# Schematic.net
KiCad netlist of a schematic drawn in Altium Designer
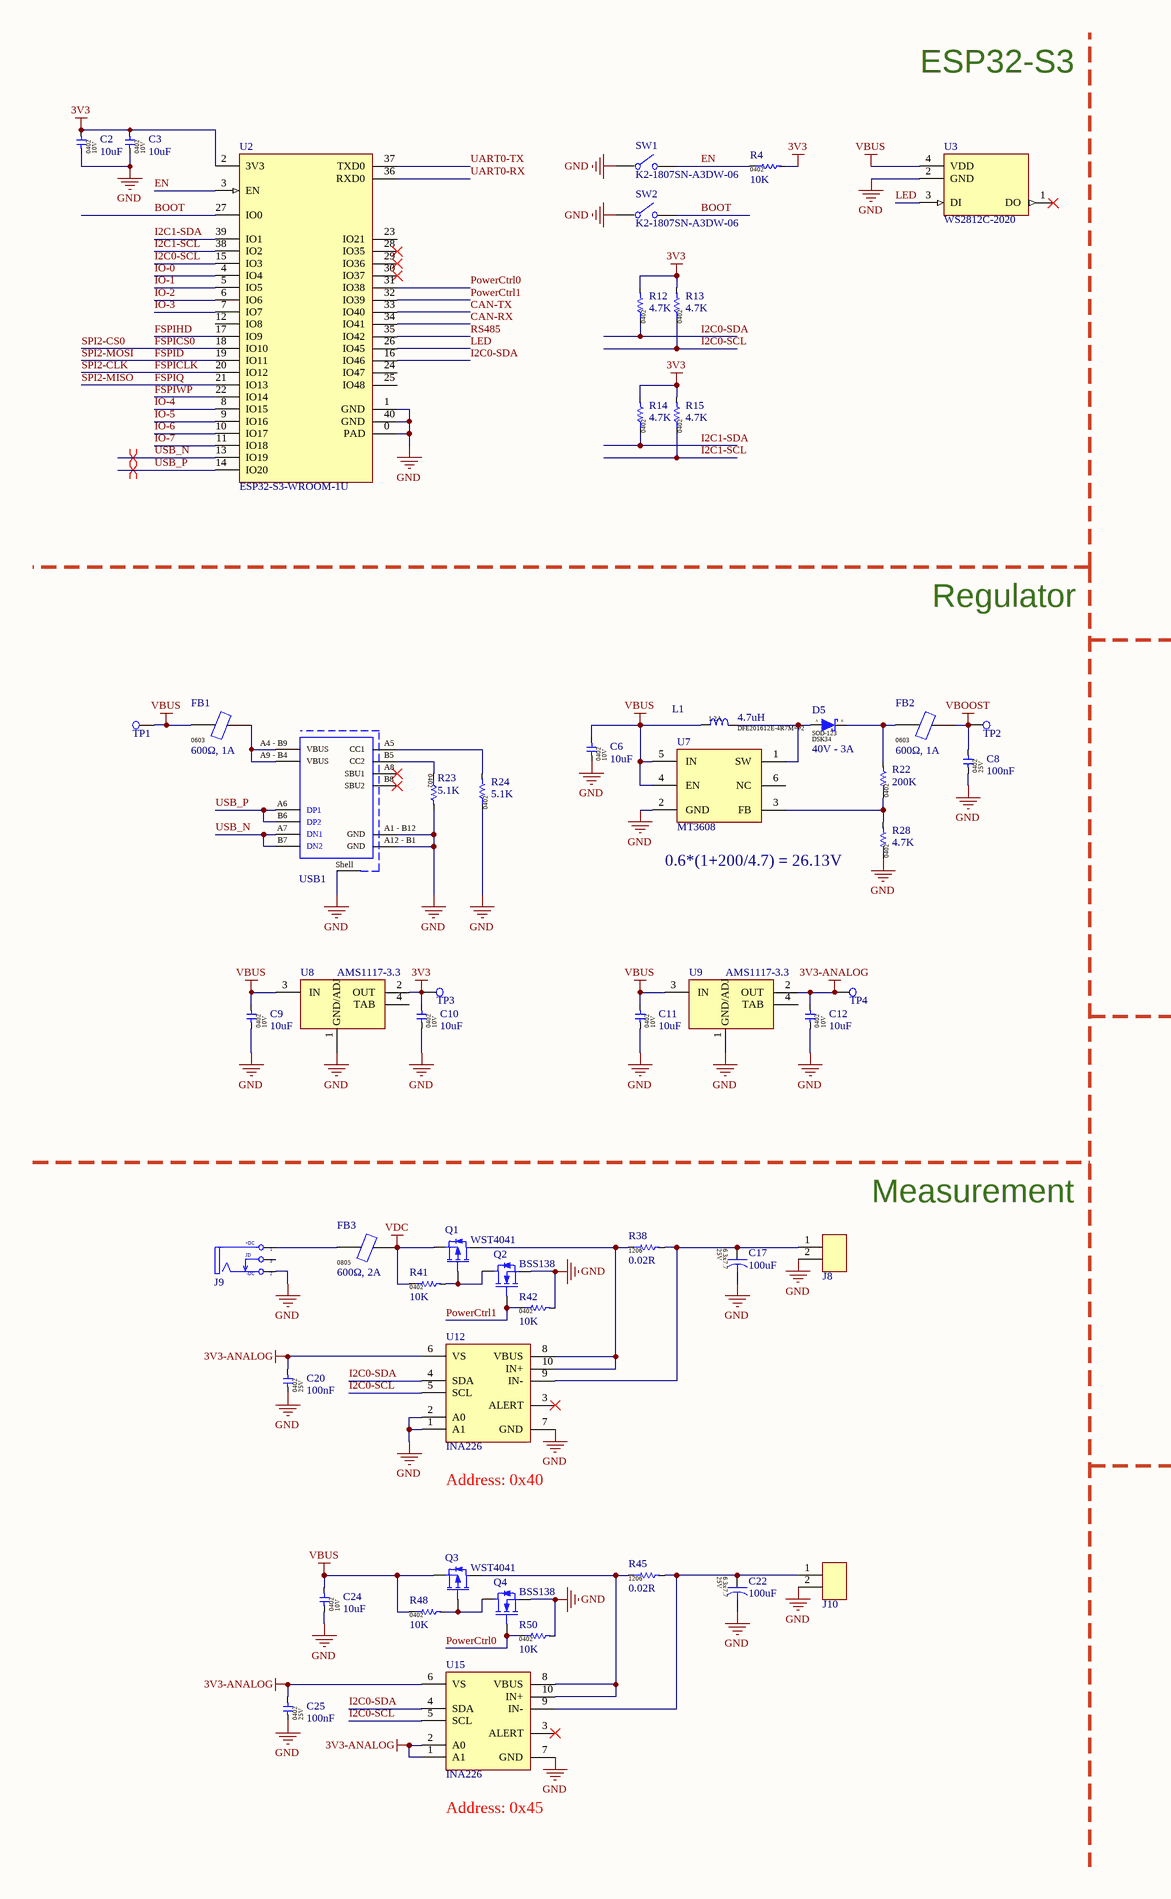
[diagram p0: Schematic.SchDoc, left]
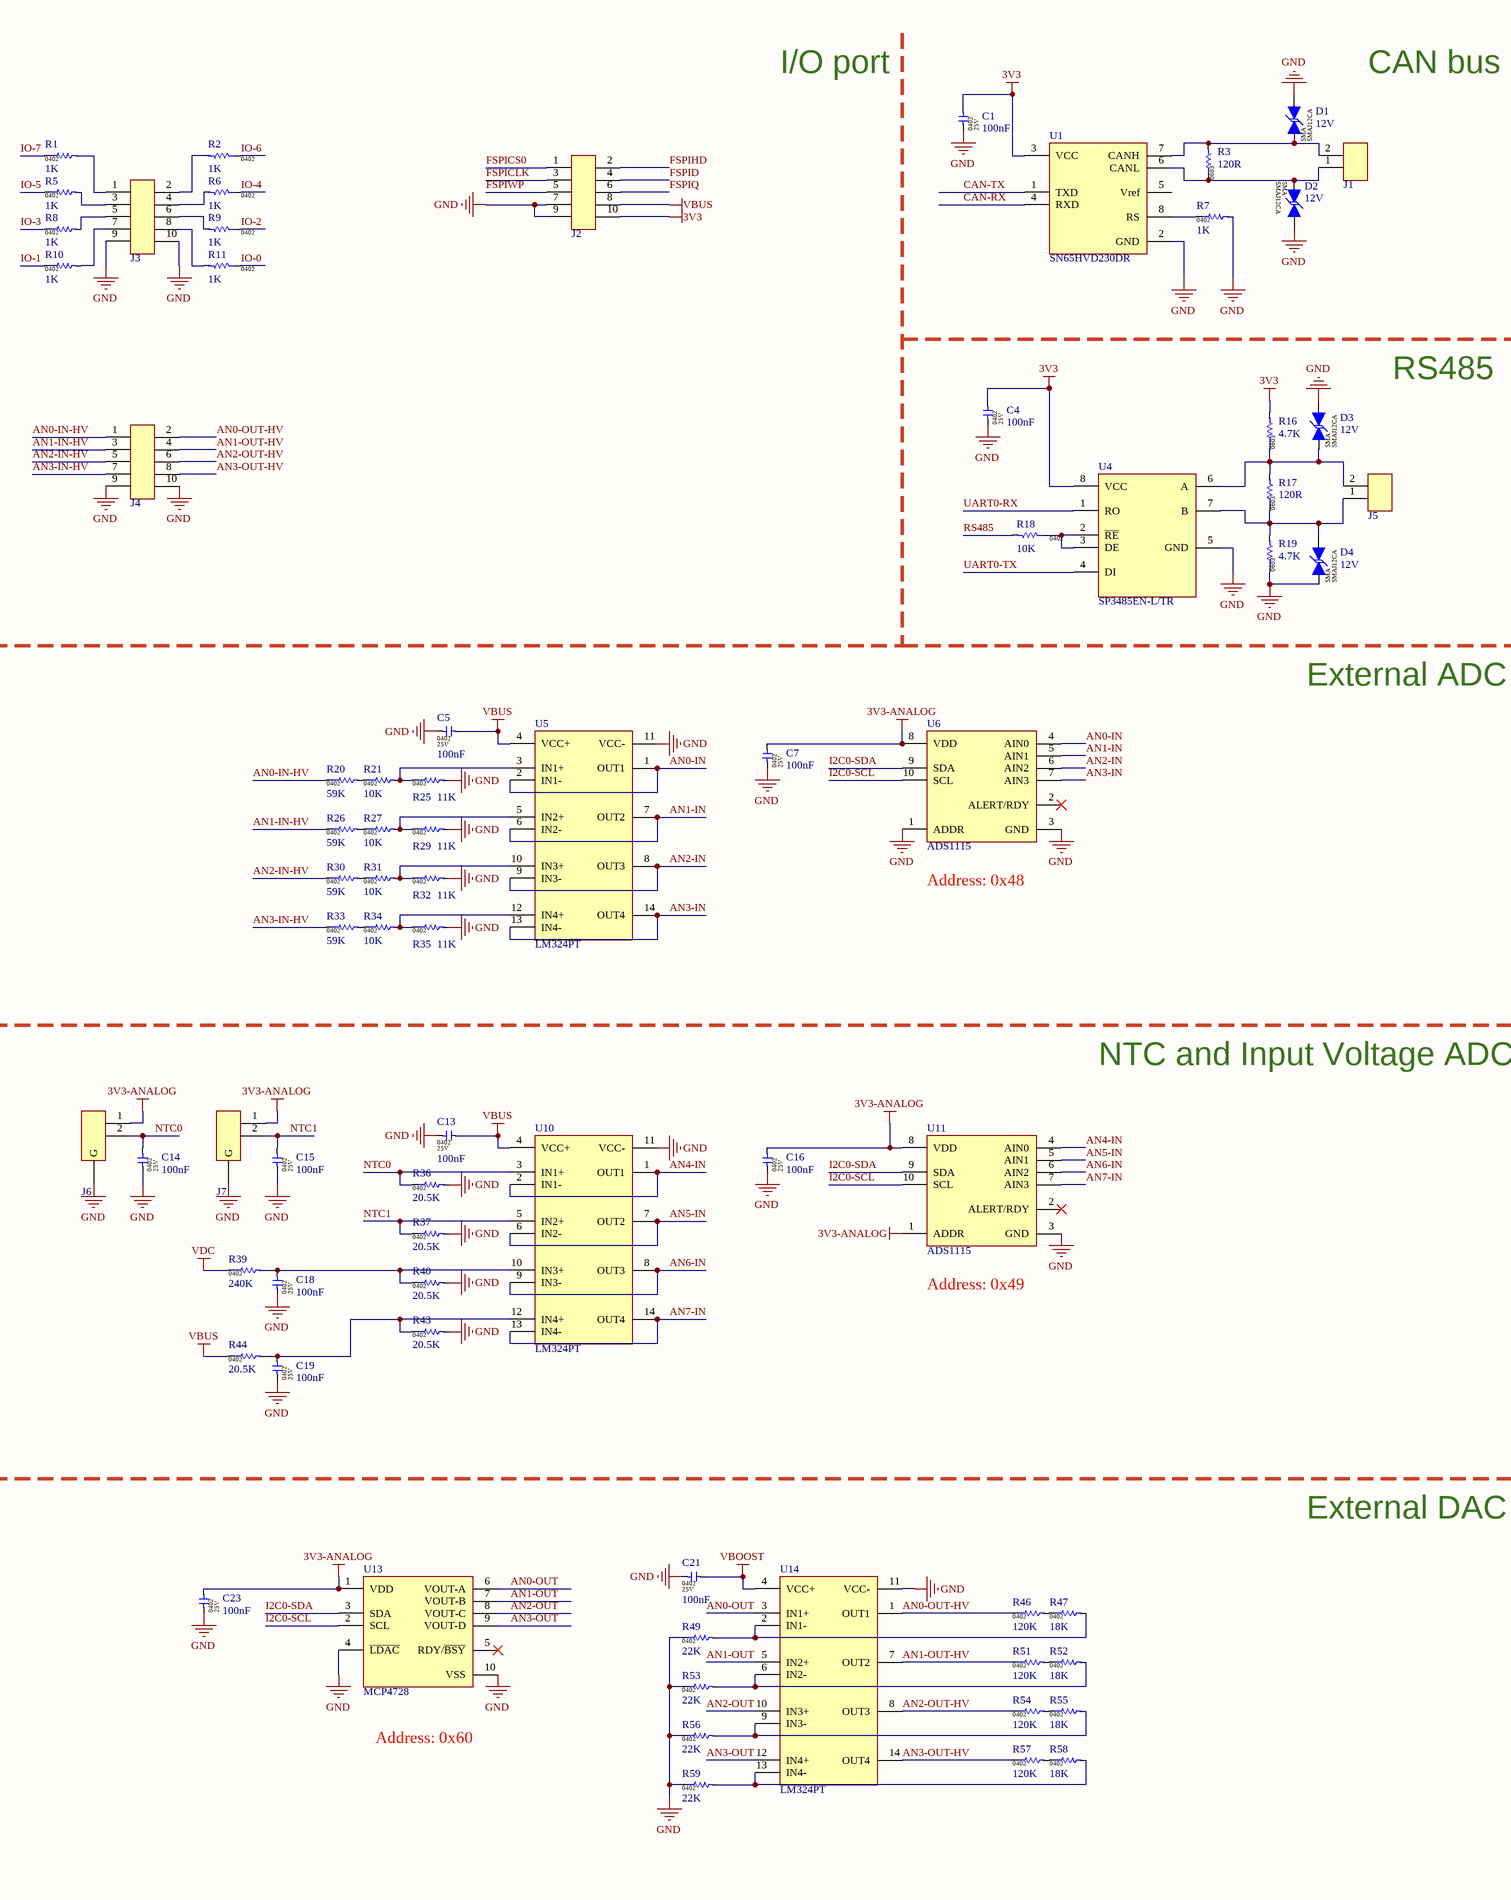
[diagram p1: Schematic.SchDoc, right]

(export (version "E")
  (design (tool "Eeschema 10.0.6"))
  (components
    (comp (ref "C1")
      (value "100nF")
      (footprint "CAP-0402")
      (description "100nF ±10% 25V X5R 0402 Multilayer Ceramic Capacitors MLCC - SMD/SMT RoHS")
      (fields (field (name "MANUFACTURE PART") "0402X104K250CT") (field (name "VOLTAGE") "25V"))
      (libsource (lib "Capacitor Database") (part "Cap-non-polarized"))
    )
    (comp (ref "C2")
      (value "10uF")
      (footprint "CAP-0402")
      (description "10V 10uF X5R ±20% 0402 Multilayer Ceramic Capacitors MLCC - SMD/SMT ROHS")
      (fields (field (name "MANUFACTURE PART") "CL05A106MP5NUNC") (field (name "VOLTAGE") "10V"))
      (libsource (lib "Capacitor Database") (part "Cap-non-polarized"))
    )
    (comp (ref "C3")
      (value "10uF")
      (footprint "CAP-0402")
      (description "10V 10uF X5R ±20% 0402 Multilayer Ceramic Capacitors MLCC - SMD/SMT ROHS")
      (fields (field (name "MANUFACTURE PART") "CL05A106MP5NUNC") (field (name "VOLTAGE") "10V"))
      (libsource (lib "Capacitor Database") (part "Cap-non-polarized"))
    )
    (comp (ref "C4")
      (value "100nF")
      (footprint "CAP-0402")
      (description "100nF ±10% 25V X5R 0402 Multilayer Ceramic Capacitors MLCC - SMD/SMT RoHS")
      (fields (field (name "MANUFACTURE PART") "0402X104K250CT") (field (name "VOLTAGE") "25V"))
      (libsource (lib "Capacitor Database") (part "Cap-non-polarized"))
    )
    (comp (ref "C5")
      (value "100nF")
      (footprint "CAP-0402")
      (description "100nF ±10% 25V X5R 0402 Multilayer Ceramic Capacitors MLCC - SMD/SMT RoHS")
      (fields (field (name "MANUFACTURE PART") "0402X104K250CT") (field (name "VOLTAGE") "25V"))
      (libsource (lib "Capacitor Database") (part "Cap-non-polarized"))
    )
    (comp (ref "C6")
      (value "10uF")
      (footprint "CAP-0402")
      (description "10V 10uF X5R ±20% 0402 Multilayer Ceramic Capacitors MLCC - SMD/SMT ROHS")
      (fields (field (name "MANUFACTURE PART") "CL05A106MP5NUNC") (field (name "VOLTAGE") "10V"))
      (libsource (lib "Capacitor Database") (part "Cap-non-polarized"))
    )
    (comp (ref "C7")
      (value "100nF")
      (footprint "CAP-0402")
      (description "100nF ±10% 25V X5R 0402 Multilayer Ceramic Capacitors MLCC - SMD/SMT RoHS")
      (fields (field (name "MANUFACTURE PART") "0402X104K250CT") (field (name "VOLTAGE") "25V"))
      (libsource (lib "Capacitor Database") (part "Cap-non-polarized"))
    )
    (comp (ref "C8")
      (value "100nF")
      (footprint "CAP-0402")
      (description "100nF ±10% 25V X5R 0402 Multilayer Ceramic Capacitors MLCC - SMD/SMT RoHS")
      (fields (field (name "MANUFACTURE PART") "0402X104K250CT") (field (name "VOLTAGE") "25V"))
      (libsource (lib "Capacitor Database") (part "Cap-non-polarized"))
    )
    (comp (ref "C9")
      (value "10uF")
      (footprint "CAP-0402")
      (description "10V 10uF X5R ±20% 0402 Multilayer Ceramic Capacitors MLCC - SMD/SMT ROHS")
      (fields (field (name "MANUFACTURE PART") "CL05A106MP5NUNC") (field (name "VOLTAGE") "10V"))
      (libsource (lib "Capacitor Database") (part "Cap-non-polarized"))
    )
    (comp (ref "C10")
      (value "10uF")
      (footprint "CAP-0402")
      (description "10V 10uF X5R ±20% 0402 Multilayer Ceramic Capacitors MLCC - SMD/SMT ROHS")
      (fields (field (name "MANUFACTURE PART") "CL05A106MP5NUNC") (field (name "VOLTAGE") "10V"))
      (libsource (lib "Capacitor Database") (part "Cap-non-polarized"))
    )
    (comp (ref "C11")
      (value "10uF")
      (footprint "CAP-0402")
      (description "10V 10uF X5R ±20% 0402 Multilayer Ceramic Capacitors MLCC - SMD/SMT ROHS")
      (fields (field (name "MANUFACTURE PART") "CL05A106MP5NUNC") (field (name "VOLTAGE") "10V"))
      (libsource (lib "Capacitor Database") (part "Cap-non-polarized"))
    )
    (comp (ref "C12")
      (value "10uF")
      (footprint "CAP-0402")
      (description "10V 10uF X5R ±20% 0402 Multilayer Ceramic Capacitors MLCC - SMD/SMT ROHS")
      (fields (field (name "MANUFACTURE PART") "CL05A106MP5NUNC") (field (name "VOLTAGE") "10V"))
      (libsource (lib "Capacitor Database") (part "Cap-non-polarized"))
    )
    (comp (ref "C13")
      (value "100nF")
      (footprint "CAP-0402")
      (description "100nF ±10% 25V X5R 0402 Multilayer Ceramic Capacitors MLCC - SMD/SMT RoHS")
      (fields (field (name "MANUFACTURE PART") "0402X104K250CT") (field (name "VOLTAGE") "25V"))
      (libsource (lib "Capacitor Database") (part "Cap-non-polarized"))
    )
    (comp (ref "C14")
      (value "100nF")
      (footprint "CAP-0402")
      (description "100nF ±10% 25V X5R 0402 Multilayer Ceramic Capacitors MLCC - SMD/SMT RoHS")
      (fields (field (name "MANUFACTURE PART") "0402X104K250CT") (field (name "VOLTAGE") "25V"))
      (libsource (lib "Capacitor Database") (part "Cap-non-polarized"))
    )
    (comp (ref "C15")
      (value "100nF")
      (footprint "CAP-0402")
      (description "100nF ±10% 25V X5R 0402 Multilayer Ceramic Capacitors MLCC - SMD/SMT RoHS")
      (fields (field (name "MANUFACTURE PART") "0402X104K250CT") (field (name "VOLTAGE") "25V"))
      (libsource (lib "Capacitor Database") (part "Cap-non-polarized"))
    )
    (comp (ref "C16")
      (value "100nF")
      (footprint "CAP-0402")
      (description "100nF ±10% 25V X5R 0402 Multilayer Ceramic Capacitors MLCC - SMD/SMT RoHS")
      (fields (field (name "MANUFACTURE PART") "0402X104K250CT") (field (name "VOLTAGE") "25V"))
      (libsource (lib "Capacitor Database") (part "Cap-non-polarized"))
    )
    (comp (ref "C17")
      (value "100uF")
      (footprint "CAP-ALU-SMD-D")
      (fields (field (name "MANUFACTURE PART") "RVT1E101M0607") (field (name "VOLTAGE") "25V"))
      (libsource (lib "Capacitor Database") (part "Cap-polarized"))
    )
    (comp (ref "C18")
      (value "100nF")
      (footprint "CAP-0402")
      (description "100nF ±10% 25V X5R 0402 Multilayer Ceramic Capacitors MLCC - SMD/SMT RoHS")
      (fields (field (name "MANUFACTURE PART") "0402X104K250CT") (field (name "VOLTAGE") "25V"))
      (libsource (lib "Capacitor Database") (part "Cap-non-polarized"))
    )
    (comp (ref "C19")
      (value "100nF")
      (footprint "CAP-0402")
      (description "100nF ±10% 25V X5R 0402 Multilayer Ceramic Capacitors MLCC - SMD/SMT RoHS")
      (fields (field (name "MANUFACTURE PART") "0402X104K250CT") (field (name "VOLTAGE") "25V"))
      (libsource (lib "Capacitor Database") (part "Cap-non-polarized"))
    )
    (comp (ref "C20")
      (value "100nF")
      (footprint "CAP-0402")
      (description "100nF ±10% 25V X5R 0402 Multilayer Ceramic Capacitors MLCC - SMD/SMT RoHS")
      (fields (field (name "MANUFACTURE PART") "0402X104K250CT") (field (name "VOLTAGE") "25V"))
      (libsource (lib "Capacitor Database") (part "Cap-non-polarized"))
    )
    (comp (ref "C21")
      (value "100nF")
      (footprint "CAP-0402")
      (description "100nF ±10% 25V X5R 0402 Multilayer Ceramic Capacitors MLCC - SMD/SMT RoHS")
      (fields (field (name "MANUFACTURE PART") "0402X104K250CT") (field (name "VOLTAGE") "25V"))
      (libsource (lib "Capacitor Database") (part "Cap-non-polarized"))
    )
    (comp (ref "C22")
      (value "100uF")
      (footprint "CAP-ALU-SMD-D")
      (fields (field (name "MANUFACTURE PART") "RVT1E101M0607") (field (name "VOLTAGE") "25V"))
      (libsource (lib "Capacitor Database") (part "Cap-polarized"))
    )
    (comp (ref "C23")
      (value "100nF")
      (footprint "CAP-0402")
      (description "100nF ±10% 25V X5R 0402 Multilayer Ceramic Capacitors MLCC - SMD/SMT RoHS")
      (fields (field (name "MANUFACTURE PART") "0402X104K250CT") (field (name "VOLTAGE") "25V"))
      (libsource (lib "Capacitor Database") (part "Cap-non-polarized"))
    )
    (comp (ref "C24")
      (value "10uF")
      (footprint "CAP-0402")
      (description "10V 10uF X5R ±20% 0402 Multilayer Ceramic Capacitors MLCC - SMD/SMT ROHS")
      (fields (field (name "MANUFACTURE PART") "CL05A106MP5NUNC") (field (name "VOLTAGE") "10V"))
      (libsource (lib "Capacitor Database") (part "Cap-non-polarized"))
    )
    (comp (ref "C25")
      (value "100nF")
      (footprint "CAP-0402")
      (description "100nF ±10% 25V X5R 0402 Multilayer Ceramic Capacitors MLCC - SMD/SMT RoHS")
      (fields (field (name "MANUFACTURE PART") "0402X104K250CT") (field (name "VOLTAGE") "25V"))
      (libsource (lib "Capacitor Database") (part "Cap-non-polarized"))
    )
    (comp (ref "D1")
      (value "12V")
      (footprint "SMA-DO-214AC (BI)")
      (description "ESD Suppressors / TVS Diodes 400W 12V 5% Bi-Directional")
      (fields (field (name "MANUFACTURE PART") "SMAJ12CA"))
      (libsource (lib "Diode Database") (part "TVS/ESD Bi diode"))
    )
    (comp (ref "D2")
      (value "12V")
      (footprint "SMA-DO-214AC (BI)")
      (description "ESD Suppressors / TVS Diodes 400W 12V 5% Bi-Directional")
      (fields (field (name "MANUFACTURE PART") "SMAJ12CA"))
      (libsource (lib "Diode Database") (part "TVS/ESD Bi diode"))
    )
    (comp (ref "D3")
      (value "12V")
      (footprint "SMA-DO-214AC (BI)")
      (description "ESD Suppressors / TVS Diodes 400W 12V 5% Bi-Directional")
      (fields (field (name "MANUFACTURE PART") "SMAJ12CA"))
      (libsource (lib "Diode Database") (part "TVS/ESD Bi diode"))
    )
    (comp (ref "D4")
      (value "12V")
      (footprint "SMA-DO-214AC (BI)")
      (description "ESD Suppressors / TVS Diodes 400W 12V 5% Bi-Directional")
      (fields (field (name "MANUFACTURE PART") "SMAJ12CA"))
      (libsource (lib "Diode Database") (part "TVS/ESD Bi diode"))
    )
    (comp (ref "D5")
      (value "40V - 3A")
      (footprint "SOD123")
      (description "40V 3A 550mV @ 3A SOD-123 Schottky Barrier Diodes (SBD) RoHS")
      (fields (field (name "MANUFACTURE PART") "DSK34"))
      (libsource (lib "Diode Database") (part "Schottky diode"))
    )
    (comp (ref "FB1")
      (value "600Ω, 1A")
      (footprint "Ferrite-0603")
      (description "600Ω @ 100MHz 1A 1 150mΩ 0603 Ferrite Beads RoHS")
      (fields (field (name "MANUFACTURE PART") "UPZ1608E601-1R0TF"))
      (libsource (lib "Filter Database") (part "Ferrite Beads"))
    )
    (comp (ref "FB2")
      (value "600Ω, 1A")
      (footprint "Ferrite-0603")
      (description "600Ω @ 100MHz 1A 1 150mΩ 0603 Ferrite Beads RoHS")
      (fields (field (name "MANUFACTURE PART") "UPZ1608E601-1R0TF"))
      (libsource (lib "Filter Database") (part "Ferrite Beads"))
    )
    (comp (ref "FB3")
      (value "600Ω, 2A")
      (footprint "Ferrite-0805")
      (description "600Ω @ 100MHz 2A ±25% 0805 Ferrite Beads ROHS")
      (fields (field (name "MANUFACTURE PART") "CBM201209U601T"))
      (libsource (lib "Filter Database") (part "Ferrite Beads"))
    )
    (comp (ref "J1")
      (value "DB301V-5.0-2P-BU-S")
      (footprint "Terminal block 2P 5.0")
      (description "1.5 -40℃~+120℃ 17.5A 250V Blue Straight pin 5mm, Screw terminal ROHS")
      (libsource (lib "") (part "Conn-2P_1"))
    )
    (comp (ref "J2")
      (value "IDC2.54-05-05PWS")
      (footprint "Conn IDC 10P-2.54H right")
      (libsource (lib "Connectors, Misc") (part "Conn-10P-2x5P"))
    )
    (comp (ref "J3")
      (value "IDC2.54-05-05PWS")
      (footprint "Conn IDC 10P-2.54H right")
      (libsource (lib "Connectors, Misc") (part "Conn-10P-2x5P"))
    )
    (comp (ref "J4")
      (value "IDC2.54-05-05PWS")
      (footprint "Conn IDC 10P-2.54H right")
      (libsource (lib "Connectors, Misc") (part "Conn-10P-2x5P"))
    )
    (comp (ref "J5")
      (value "DB301V-5.0-2P-BU-S")
      (footprint "Terminal block 2P 5.0")
      (description "1.5 -40℃~+120℃ 17.5A 250V Blue Straight pin 5mm, Screw terminal ROHS")
      (libsource (lib "") (part "Conn-2P_1"))
    )
    (comp (ref "J6")
      (value "S2B-XH-SM4-TB(LF)(SN)")
      (footprint "XH-2.54-2Pin-SMT")
      (description "XH Header Male Pin 0.098\"(2.50mm) 2 SMD,P=2.5mm Wire To Board / Wire To Wire Connector RoHS")
      (libsource (lib "Connectors, Misc") (part "Conn-2P_PAD"))
    )
    (comp (ref "J7")
      (value "S2B-XH-SM4-TB(LF)(SN)")
      (footprint "XH-2.54-2Pin-SMT")
      (description "XH Header Male Pin 0.098\"(2.50mm) 2 SMD,P=2.5mm Wire To Board / Wire To Wire Connector RoHS")
      (libsource (lib "Connectors, Misc") (part "Conn-2P_PAD"))
    )
    (comp (ref "J8")
      (value "DB301V-5.0-2P-BU-S")
      (footprint "Terminal block 2P 5.0")
      (description "1.5 -40℃~+120℃ 17.5A 250V Blue Straight pin 5mm, Screw terminal ROHS")
      (libsource (lib "Connectors, Misc") (part "Conn-2P"))
    )
    (comp (ref "J9")
      (value "DC-044A-2.5A-2.0")
      (footprint "Jack DC 5.5-2.5mm")
      (description "DC Power Receptacle 260℃ Brass -20℃~+70℃ 2mm 6mm 2.5A 24V Plugin DC Power Connector ROHS")
      (libsource (lib "Connectors, Misc") (part "Jack DC"))
    )
    (comp (ref "J10")
      (value "DB301V-5.0-2P-BU-S")
      (footprint "Terminal block 2P 5.0")
      (description "1.5 -40℃~+120℃ 17.5A 250V Blue Straight pin 5mm, Screw terminal ROHS")
      (libsource (lib "Connectors, Misc") (part "Conn-2P"))
    )
    (comp (ref "L1")
      (value "4.7uH")
      (footprint "IND-201612")
      (description "1.2A 4.7uH ±20% 1.8A 0806 Power Inductors ROHS")
      (fields (field (name "MANUFACTURE PART") "DFE201612E-4R7M=P2"))
      (libsource (lib "Inductor Database") (part "Inductor"))
    )
    (comp (ref "Q1")
      (value "WST4041")
      (footprint "SOT23-3")
      (description "1.4W 40V 6A 2.2V 250uA P Channel 0.04Ω 3A,10V SOT-23(SOT-23-3) MOSFETs ROHS")
      (libsource (lib "Transistor Database") (part "Generic P-Mosfet"))
    )
    (comp (ref "Q2")
      (value "BSS138")
      (footprint "SOT23-3")
      (description "N-Channel 50V 220mA 1.5V @ 1mA 3.5Ω @ 220mA,10V 360mW SOT-23(SOT-23-3) MOSFETs RoHS")
      (libsource (lib "Transistor Database") (part "Generic N-Mosfet"))
    )
    (comp (ref "Q3")
      (value "WST4041")
      (footprint "SOT23-3")
      (description "1.4W 40V 6A 2.2V 250uA P Channel 0.04Ω 3A,10V SOT-23(SOT-23-3) MOSFETs ROHS")
      (libsource (lib "Transistor Database") (part "Generic P-Mosfet"))
    )
    (comp (ref "Q4")
      (value "BSS138")
      (footprint "SOT23-3")
      (description "N-Channel 50V 220mA 1.5V @ 1mA 3.5Ω @ 220mA,10V 360mW SOT-23(SOT-23-3) MOSFETs RoHS")
      (libsource (lib "Transistor Database") (part "Generic N-Mosfet"))
    )
    (comp (ref "R1")
      (value "1K")
      (footprint "RES-0402")
      (description "1kΩ ±1% 1/16W ±100ppm/℃ 0402 Chip Resistor - Surface Mount RoHS")
      (fields (field (name "MANUFACTURE PART") "WR04X1001FTL"))
      (libsource (lib "Resistor Database") (part "Resistor"))
    )
    (comp (ref "R2")
      (value "1K")
      (footprint "RES-0402")
      (description "1kΩ ±1% 1/16W ±100ppm/℃ 0402 Chip Resistor - Surface Mount RoHS")
      (fields (field (name "MANUFACTURE PART") "WR04X1001FTL"))
      (libsource (lib "Resistor Database") (part "Resistor"))
    )
    (comp (ref "R3")
      (value "120R")
      (footprint "RES-0603")
      (description "100mW 75V ±100ppm/℃ ±1% -55℃~+155℃ 120Ω 0603 Chip Resistor - Surface Mount ROHS")
      (fields (field (name "MANUFACTURE PART") "RC0603FR-07120RL"))
      (libsource (lib "Resistor Database") (part "Resistor"))
    )
    (comp (ref "R4")
      (value "10K")
      (footprint "RES-0402")
      (description "10kΩ ±1% 1/16W ±100ppm/℃ 0402 Chip Resistor - Surface Mount RoHS")
      (fields (field (name "MANUFACTURE PART") "WR04X1002FTL"))
      (libsource (lib "Resistor Database") (part "Resistor"))
    )
    (comp (ref "R5")
      (value "1K")
      (footprint "RES-0402")
      (description "1kΩ ±1% 1/16W ±100ppm/℃ 0402 Chip Resistor - Surface Mount RoHS")
      (fields (field (name "MANUFACTURE PART") "WR04X1001FTL"))
      (libsource (lib "Resistor Database") (part "Resistor"))
    )
    (comp (ref "R6")
      (value "1K")
      (footprint "RES-0402")
      (description "1kΩ ±1% 1/16W ±100ppm/℃ 0402 Chip Resistor - Surface Mount RoHS")
      (fields (field (name "MANUFACTURE PART") "WR04X1001FTL"))
      (libsource (lib "Resistor Database") (part "Resistor"))
    )
    (comp (ref "R7")
      (value "1K")
      (footprint "RES-0402")
      (description "1kΩ ±1% 1/16W ±100ppm/℃ 0402 Chip Resistor - Surface Mount RoHS")
      (fields (field (name "MANUFACTURE PART") "WR04X1001FTL"))
      (libsource (lib "Resistor Database") (part "Resistor"))
    )
    (comp (ref "R8")
      (value "1K")
      (footprint "RES-0402")
      (description "1kΩ ±1% 1/16W ±100ppm/℃ 0402 Chip Resistor - Surface Mount RoHS")
      (fields (field (name "MANUFACTURE PART") "WR04X1001FTL"))
      (libsource (lib "Resistor Database") (part "Resistor"))
    )
    (comp (ref "R9")
      (value "1K")
      (footprint "RES-0402")
      (description "1kΩ ±1% 1/16W ±100ppm/℃ 0402 Chip Resistor - Surface Mount RoHS")
      (fields (field (name "MANUFACTURE PART") "WR04X1001FTL"))
      (libsource (lib "Resistor Database") (part "Resistor"))
    )
    (comp (ref "R10")
      (value "1K")
      (footprint "RES-0402")
      (description "1kΩ ±1% 1/16W ±100ppm/℃ 0402 Chip Resistor - Surface Mount RoHS")
      (fields (field (name "MANUFACTURE PART") "WR04X1001FTL"))
      (libsource (lib "Resistor Database") (part "Resistor"))
    )
    (comp (ref "R11")
      (value "1K")
      (footprint "RES-0402")
      (description "1kΩ ±1% 1/16W ±100ppm/℃ 0402 Chip Resistor - Surface Mount RoHS")
      (fields (field (name "MANUFACTURE PART") "WR04X1001FTL"))
      (libsource (lib "Resistor Database") (part "Resistor"))
    )
    (comp (ref "R12")
      (value "4.7K")
      (footprint "RES-0402")
      (description "4.7kΩ ±1% 1/16W ±100ppm/℃ 0402 Chip Resistor - Surface Mount RoHS")
      (fields (field (name "MANUFACTURE PART") "WR04X4701FTL"))
      (libsource (lib "Resistor Database") (part "Resistor"))
    )
    (comp (ref "R13")
      (value "4.7K")
      (footprint "RES-0402")
      (description "4.7kΩ ±1% 1/16W ±100ppm/℃ 0402 Chip Resistor - Surface Mount RoHS")
      (fields (field (name "MANUFACTURE PART") "WR04X4701FTL"))
      (libsource (lib "Resistor Database") (part "Resistor"))
    )
    (comp (ref "R14")
      (value "4.7K")
      (footprint "RES-0402")
      (description "4.7kΩ ±1% 1/16W ±100ppm/℃ 0402 Chip Resistor - Surface Mount RoHS")
      (fields (field (name "MANUFACTURE PART") "WR04X4701FTL"))
      (libsource (lib "Resistor Database") (part "Resistor"))
    )
    (comp (ref "R15")
      (value "4.7K")
      (footprint "RES-0402")
      (description "4.7kΩ ±1% 1/16W ±100ppm/℃ 0402 Chip Resistor - Surface Mount RoHS")
      (fields (field (name "MANUFACTURE PART") "WR04X4701FTL"))
      (libsource (lib "Resistor Database") (part "Resistor"))
    )
    (comp (ref "R16")
      (value "4.7K")
      (footprint "RES-0603")
      (description "4.7kΩ ±1% 0.1W ±100ppm/℃ 0603 Chip Resistor - Surface Mount RoHS")
      (fields (field (name "MANUFACTURE PART") "WR06X4701FTL"))
      (libsource (lib "Resistor Database") (part "Resistor"))
    )
    (comp (ref "R17")
      (value "120R")
      (footprint "RES-0603")
      (description "100mW 75V ±100ppm/℃ ±1% -55℃~+155℃ 120Ω 0603 Chip Resistor - Surface Mount ROHS")
      (fields (field (name "MANUFACTURE PART") "RC0603FR-07120RL"))
      (libsource (lib "Resistor Database") (part "Resistor"))
    )
    (comp (ref "R18")
      (value "10K")
      (footprint "RES-0402")
      (description "10kΩ ±1% 1/16W ±100ppm/℃ 0402 Chip Resistor - Surface Mount RoHS")
      (fields (field (name "MANUFACTURE PART") "WR04X1002FTL"))
      (libsource (lib "Resistor Database") (part "Resistor"))
    )
    (comp (ref "R19")
      (value "4.7K")
      (footprint "RES-0603")
      (description "4.7kΩ ±1% 0.1W ±100ppm/℃ 0603 Chip Resistor - Surface Mount RoHS")
      (fields (field (name "MANUFACTURE PART") "WR06X4701FTL"))
      (libsource (lib "Resistor Database") (part "Resistor"))
    )
    (comp (ref "R20")
      (value "59K")
      (footprint "RES-0402")
      (description "±1% 1/16W 50V ±100ppm/℃ -55℃~+155℃ 59kΩ 0402 Chip Resistor - Surface Mount ROHS")
      (fields (field (name "MANUFACTURE PART") "WR04X5902FTL"))
      (libsource (lib "Resistor Database") (part "Resistor"))
    )
    (comp (ref "R21")
      (value "10K")
      (footprint "RES-0402")
      (description "10kΩ ±1% 1/16W ±100ppm/℃ 0402 Chip Resistor - Surface Mount RoHS")
      (fields (field (name "MANUFACTURE PART") "WR04X1002FTL"))
      (libsource (lib "Resistor Database") (part "Resistor"))
    )
    (comp (ref "R22")
      (value "200K")
      (footprint "RES-0402")
      (description "200kΩ ±1% 1/16W ±100ppm/℃ 0402 Chip Resistor - Surface Mount RoHS")
      (fields (field (name "MANUFACTURE PART") "WR04X2003FTL"))
      (libsource (lib "Resistor Database") (part "Resistor"))
    )
    (comp (ref "R23")
      (value "5.1K")
      (footprint "RES-0402")
      (description "5.1kΩ ±1% 1/16W ±100ppm/℃ 0402 Chip Resistor - Surface Mount RoHS")
      (fields (field (name "MANUFACTURE PART") "WR04X5101FTL"))
      (libsource (lib "Resistor Database") (part "Resistor"))
    )
    (comp (ref "R24")
      (value "5.1K")
      (footprint "RES-0402")
      (description "5.1kΩ ±1% 1/16W ±100ppm/℃ 0402 Chip Resistor - Surface Mount RoHS")
      (fields (field (name "MANUFACTURE PART") "WR04X5101FTL"))
      (libsource (lib "Resistor Database") (part "Resistor"))
    )
    (comp (ref "R25")
      (value "11K")
      (footprint "RES-0402")
      (description "62.5mW Thick Film Resistors 50V ±100ppm/℃ ±1% 11kΩ 0402 Chip Resistor - Surface Mount ROHS")
      (fields (field (name "MANUFACTURE PART") "RC0402FR-0711KL"))
      (libsource (lib "Resistor Database") (part "Resistor"))
    )
    (comp (ref "R26")
      (value "59K")
      (footprint "RES-0402")
      (description "±1% 1/16W 50V ±100ppm/℃ -55℃~+155℃ 59kΩ 0402 Chip Resistor - Surface Mount ROHS")
      (fields (field (name "MANUFACTURE PART") "WR04X5902FTL"))
      (libsource (lib "Resistor Database") (part "Resistor"))
    )
    (comp (ref "R27")
      (value "10K")
      (footprint "RES-0402")
      (description "10kΩ ±1% 1/16W ±100ppm/℃ 0402 Chip Resistor - Surface Mount RoHS")
      (fields (field (name "MANUFACTURE PART") "WR04X1002FTL"))
      (libsource (lib "Resistor Database") (part "Resistor"))
    )
    (comp (ref "R28")
      (value "4.7K")
      (footprint "RES-0402")
      (description "4.7kΩ ±1% 1/16W ±100ppm/℃ 0402 Chip Resistor - Surface Mount RoHS")
      (fields (field (name "MANUFACTURE PART") "WR04X4701FTL"))
      (libsource (lib "Resistor Database") (part "Resistor"))
    )
    (comp (ref "R29")
      (value "11K")
      (footprint "RES-0402")
      (description "62.5mW Thick Film Resistors 50V ±100ppm/℃ ±1% 11kΩ 0402 Chip Resistor - Surface Mount ROHS")
      (fields (field (name "MANUFACTURE PART") "RC0402FR-0711KL"))
      (libsource (lib "Resistor Database") (part "Resistor"))
    )
    (comp (ref "R30")
      (value "59K")
      (footprint "RES-0402")
      (description "±1% 1/16W 50V ±100ppm/℃ -55℃~+155℃ 59kΩ 0402 Chip Resistor - Surface Mount ROHS")
      (fields (field (name "MANUFACTURE PART") "WR04X5902FTL"))
      (libsource (lib "Resistor Database") (part "Resistor"))
    )
    (comp (ref "R31")
      (value "10K")
      (footprint "RES-0402")
      (description "10kΩ ±1% 1/16W ±100ppm/℃ 0402 Chip Resistor - Surface Mount RoHS")
      (fields (field (name "MANUFACTURE PART") "WR04X1002FTL"))
      (libsource (lib "Resistor Database") (part "Resistor"))
    )
    (comp (ref "R32")
      (value "11K")
      (footprint "RES-0402")
      (description "62.5mW Thick Film Resistors 50V ±100ppm/℃ ±1% 11kΩ 0402 Chip Resistor - Surface Mount ROHS")
      (fields (field (name "MANUFACTURE PART") "RC0402FR-0711KL"))
      (libsource (lib "Resistor Database") (part "Resistor"))
    )
    (comp (ref "R33")
      (value "59K")
      (footprint "RES-0402")
      (description "±1% 1/16W 50V ±100ppm/℃ -55℃~+155℃ 59kΩ 0402 Chip Resistor - Surface Mount ROHS")
      (fields (field (name "MANUFACTURE PART") "WR04X5902FTL"))
      (libsource (lib "Resistor Database") (part "Resistor"))
    )
    (comp (ref "R34")
      (value "10K")
      (footprint "RES-0402")
      (description "10kΩ ±1% 1/16W ±100ppm/℃ 0402 Chip Resistor - Surface Mount RoHS")
      (fields (field (name "MANUFACTURE PART") "WR04X1002FTL"))
      (libsource (lib "Resistor Database") (part "Resistor"))
    )
    (comp (ref "R35")
      (value "11K")
      (footprint "RES-0402")
      (description "62.5mW Thick Film Resistors 50V ±100ppm/℃ ±1% 11kΩ 0402 Chip Resistor - Surface Mount ROHS")
      (fields (field (name "MANUFACTURE PART") "RC0402FR-0711KL"))
      (libsource (lib "Resistor Database") (part "Resistor"))
    )
    (comp (ref "R36")
      (value "20.5K")
      (footprint "RES-0402")
      (description "±1% 20.5kΩ 1/16W ±100ppm/℃ 0402 Chip Resistor - Surface Mount ROHS")
      (fields (field (name "MANUFACTURE PART") "WR04X2052FTL"))
      (libsource (lib "Resistor Database") (part "Resistor"))
    )
    (comp (ref "R37")
      (value "20.5K")
      (footprint "RES-0402")
      (description "±1% 20.5kΩ 1/16W ±100ppm/℃ 0402 Chip Resistor - Surface Mount ROHS")
      (fields (field (name "MANUFACTURE PART") "WR04X2052FTL"))
      (libsource (lib "Resistor Database") (part "Resistor"))
    )
    (comp (ref "R38")
      (value "0.02R")
      (footprint "RES-1206")
      (description "1W ±100ppm/℃ ±1% 20mΩ 1206 Chip Resistor - Surface Mount ROHS")
      (fields (field (name "MANUFACTURE PART") "PA1206FRF470R02L"))
      (libsource (lib "Resistor Database") (part "Resistor"))
    )
    (comp (ref "R39")
      (value "240K")
      (footprint "RES-0402")
      (description "62.5mW Thick Film Resistors ±100ppm/℃ ±1% 240kΩ 0402 Chip Resistor - Surface Mount ROHS")
      (fields (field (name "MANUFACTURE PART") "RC0402FR-07240KL"))
      (libsource (lib "Resistor Database") (part "Resistor"))
    )
    (comp (ref "R40")
      (value "20.5K")
      (footprint "RES-0402")
      (description "±1% 20.5kΩ 1/16W ±100ppm/℃ 0402 Chip Resistor - Surface Mount ROHS")
      (fields (field (name "MANUFACTURE PART") "WR04X2052FTL"))
      (libsource (lib "Resistor Database") (part "Resistor"))
    )
    (comp (ref "R41")
      (value "10K")
      (footprint "RES-0402")
      (description "10kΩ ±1% 1/16W ±100ppm/℃ 0402 Chip Resistor - Surface Mount RoHS")
      (fields (field (name "MANUFACTURE PART") "WR04X1002FTL"))
      (libsource (lib "Resistor Database") (part "Resistor"))
    )
    (comp (ref "R42")
      (value "10K")
      (footprint "RES-0402")
      (description "10kΩ ±1% 1/16W ±100ppm/℃ 0402 Chip Resistor - Surface Mount RoHS")
      (fields (field (name "MANUFACTURE PART") "WR04X1002FTL"))
      (libsource (lib "Resistor Database") (part "Resistor"))
    )
    (comp (ref "R43")
      (value "20.5K")
      (footprint "RES-0402")
      (description "±1% 20.5kΩ 1/16W ±100ppm/℃ 0402 Chip Resistor - Surface Mount ROHS")
      (fields (field (name "MANUFACTURE PART") "WR04X2052FTL"))
      (libsource (lib "Resistor Database") (part "Resistor"))
    )
    (comp (ref "R44")
      (value "20.5K")
      (footprint "RES-0402")
      (description "±1% 20.5kΩ 1/16W ±100ppm/℃ 0402 Chip Resistor - Surface Mount ROHS")
      (fields (field (name "MANUFACTURE PART") "WR04X2052FTL"))
      (libsource (lib "Resistor Database") (part "Resistor"))
    )
    (comp (ref "R45")
      (value "0.02R")
      (footprint "RES-1206")
      (description "1W ±100ppm/℃ ±1% 20mΩ 1206 Chip Resistor - Surface Mount ROHS")
      (fields (field (name "MANUFACTURE PART") "PA1206FRF470R02L"))
      (libsource (lib "Resistor Database") (part "Resistor"))
    )
    (comp (ref "R46")
      (value "120K")
      (footprint "RES-0402")
      (description "120kΩ ±1% 1/16W ±100ppm/℃ 0402 Chip Resistor - Surface Mount RoHS")
      (fields (field (name "MANUFACTURE PART") "WR04X1203FTL"))
      (libsource (lib "Resistor Database") (part "Resistor"))
    )
    (comp (ref "R47")
      (value "18K")
      (footprint "RES-0402")
      (description "±1% 1/16W 50V ±100ppm/℃ -55℃~+155℃ 18kΩ 0402 Chip Resistor - Surface Mount ROHS")
      (fields (field (name "MANUFACTURE PART") "WR04X1802FTL"))
      (libsource (lib "Resistor Database") (part "Resistor"))
    )
    (comp (ref "R48")
      (value "10K")
      (footprint "RES-0402")
      (description "10kΩ ±1% 1/16W ±100ppm/℃ 0402 Chip Resistor - Surface Mount RoHS")
      (fields (field (name "MANUFACTURE PART") "WR04X1002FTL"))
      (libsource (lib "Resistor Database") (part "Resistor"))
    )
    (comp (ref "R49")
      (value "22K")
      (footprint "RES-0402")
      (description "22kΩ 1/16W ±1% 0402 Chip Resistor - Surface Mount ROHS")
      (fields (field (name "MANUFACTURE PART") "WR04X2202FTL"))
      (libsource (lib "Resistor Database") (part "Resistor"))
    )
    (comp (ref "R50")
      (value "10K")
      (footprint "RES-0402")
      (description "10kΩ ±1% 1/16W ±100ppm/℃ 0402 Chip Resistor - Surface Mount RoHS")
      (fields (field (name "MANUFACTURE PART") "WR04X1002FTL"))
      (libsource (lib "Resistor Database") (part "Resistor"))
    )
    (comp (ref "R51")
      (value "120K")
      (footprint "RES-0402")
      (description "120kΩ ±1% 1/16W ±100ppm/℃ 0402 Chip Resistor - Surface Mount RoHS")
      (fields (field (name "MANUFACTURE PART") "WR04X1203FTL"))
      (libsource (lib "Resistor Database") (part "Resistor"))
    )
    (comp (ref "R52")
      (value "18K")
      (footprint "RES-0402")
      (description "±1% 1/16W 50V ±100ppm/℃ -55℃~+155℃ 18kΩ 0402 Chip Resistor - Surface Mount ROHS")
      (fields (field (name "MANUFACTURE PART") "WR04X1802FTL"))
      (libsource (lib "Resistor Database") (part "Resistor"))
    )
    (comp (ref "R53")
      (value "22K")
      (footprint "RES-0402")
      (description "22kΩ 1/16W ±1% 0402 Chip Resistor - Surface Mount ROHS")
      (fields (field (name "MANUFACTURE PART") "WR04X2202FTL"))
      (libsource (lib "Resistor Database") (part "Resistor"))
    )
    (comp (ref "R54")
      (value "120K")
      (footprint "RES-0402")
      (description "120kΩ ±1% 1/16W ±100ppm/℃ 0402 Chip Resistor - Surface Mount RoHS")
      (fields (field (name "MANUFACTURE PART") "WR04X1203FTL"))
      (libsource (lib "Resistor Database") (part "Resistor"))
    )
    (comp (ref "R55")
      (value "18K")
      (footprint "RES-0402")
      (description "±1% 1/16W 50V ±100ppm/℃ -55℃~+155℃ 18kΩ 0402 Chip Resistor - Surface Mount ROHS")
      (fields (field (name "MANUFACTURE PART") "WR04X1802FTL"))
      (libsource (lib "Resistor Database") (part "Resistor"))
    )
    (comp (ref "R56")
      (value "22K")
      (footprint "RES-0402")
      (description "22kΩ 1/16W ±1% 0402 Chip Resistor - Surface Mount ROHS")
      (fields (field (name "MANUFACTURE PART") "WR04X2202FTL"))
      (libsource (lib "Resistor Database") (part "Resistor"))
    )
    (comp (ref "R57")
      (value "120K")
      (footprint "RES-0402")
      (description "120kΩ ±1% 1/16W ±100ppm/℃ 0402 Chip Resistor - Surface Mount RoHS")
      (fields (field (name "MANUFACTURE PART") "WR04X1203FTL"))
      (libsource (lib "Resistor Database") (part "Resistor"))
    )
    (comp (ref "R58")
      (value "18K")
      (footprint "RES-0402")
      (description "±1% 1/16W 50V ±100ppm/℃ -55℃~+155℃ 18kΩ 0402 Chip Resistor - Surface Mount ROHS")
      (fields (field (name "MANUFACTURE PART") "WR04X1802FTL"))
      (libsource (lib "Resistor Database") (part "Resistor"))
    )
    (comp (ref "R59")
      (value "22K")
      (footprint "RES-0402")
      (description "22kΩ 1/16W ±1% 0402 Chip Resistor - Surface Mount ROHS")
      (fields (field (name "MANUFACTURE PART") "WR04X2202FTL"))
      (libsource (lib "Resistor Database") (part "Resistor"))
    )
    (comp (ref "SW1")
      (value "K2-1807SN-A3DW-06")
      (footprint "SW - TYPE 3")
      (description "SMD,3×4×2.0mm Tactile Switches RoHS")
      (libsource (lib "Connectors, Misc") (part "Tactile Switch"))
    )
    (comp (ref "SW2")
      (value "K2-1807SN-A3DW-06")
      (footprint "SW - TYPE 3")
      (description "SMD,3×4×2.0mm Tactile Switches RoHS")
      (libsource (lib "Connectors, Misc") (part "Tactile Switch"))
    )
    (comp (ref "TP1")
      (value "N/A")
      (footprint "Test point")
      (description "A point used for measure.")
      (libsource (lib "Connectors, Misc") (part "Test point"))
    )
    (comp (ref "TP2")
      (value "N/A")
      (footprint "Test point")
      (description "A point used for measure.")
      (libsource (lib "Connectors, Misc") (part "Test point"))
    )
    (comp (ref "TP3")
      (value "N/A")
      (footprint "Test point")
      (description "A point used for measure.")
      (libsource (lib "Connectors, Misc") (part "Test point"))
    )
    (comp (ref "TP4")
      (value "N/A")
      (footprint "Test point")
      (description "A point used for measure.")
      (libsource (lib "Connectors, Misc") (part "Test point"))
    )
    (comp (ref "U1")
      (value "SN65HVD230DR")
      (footprint "SOP-8")
      (description "3.3-V CAN Bus Transceivers")
      (libsource (lib "IC Database") (part "SN65HVD23X"))
    )
    (comp (ref "U2")
      (value "ESP32-S3-WROOM-1U")
      (footprint "ESP32-S3-WROOM-1U")
      (description "Module WiFi Modules ROHS")
      (libsource (lib "IC Database") (part "ESP32-S3-WROOM-1/1U"))
    )
    (comp (ref "U3")
      (value "WS2812C-2020")
      (footprint "WS2812C-2020")
      (description "2.0x2.0mm Light Emitting Diodes (LED)")
      (libsource (lib "Led Database") (part "WS2812C-2020"))
    )
    (comp (ref "U4")
      (value "SP3485EN-L/TR")
      (footprint "SOP-8")
      (description "RS-422/RS-485 Interface IC 3.3V LoPwr Half-Dup RS485w/10Mbps Data")
      (libsource (lib "IC Database") (part "SP3485"))
    )
    (comp (ref "U5")
      (value "LM324PT")
      (footprint "TSSOP-14")
      (description "Low-power quad operational amplifiers")
      (libsource (lib "IC Database") (part "LM324PT"))
    )
    (comp (ref "U6")
      (value "ADS1115")
      (footprint "VSSOP-10")
      (libsource (lib "IC Database") (part "ADS1115"))
    )
    (comp (ref "U7")
      (value "MT3608")
      (footprint "SOT23-6")
      (description "High Efficiency 1.2MHz 2A Step Up Converter, 2V to 24V Input, Up to 28V Output")
      (libsource (lib "Regulator Database") (part "MT3608"))
    )
    (comp (ref "U8")
      (value "AMS1117-3.3")
      (footprint "SOT223")
      (description "Fixed 15V 3.3V 1.3V @ 800mA SOT-223 Dropout Regulators(LDO) RoHS")
      (libsource (lib "Regulator Database") (part "AMS1117"))
    )
    (comp (ref "U9")
      (value "AMS1117-3.3")
      (footprint "SOT223")
      (description "Fixed 15V 3.3V 1.3V @ 800mA SOT-223 Dropout Regulators(LDO) RoHS")
      (libsource (lib "Regulator Database") (part "AMS1117"))
    )
    (comp (ref "U10")
      (value "LM324PT")
      (footprint "TSSOP-14")
      (description "Low-power quad operational amplifiers")
      (libsource (lib "IC Database") (part "LM324PT"))
    )
    (comp (ref "U11")
      (value "ADS1115")
      (footprint "VSSOP-10")
      (libsource (lib "IC Database") (part "ADS1115"))
    )
    (comp (ref "U12") (value "INA226") (footprint "VSSOP-10") (libsource (lib "IC Database") (part "INA226")))
    (comp (ref "U13")
      (value "MCP4728")
      (footprint "MSOP-10")
      (description "12-Bit Quad Output DAC w/EEPROM and I2")
      (libsource (lib "IC Database") (part "MCP4728"))
    )
    (comp (ref "U14")
      (value "LM324PT")
      (footprint "TSSOP-14")
      (description "Low-power quad operational amplifiers")
      (libsource (lib "IC Database") (part "LM324PT"))
    )
    (comp (ref "U15") (value "INA226") (footprint "VSSOP-10") (libsource (lib "IC Database") (part "INA226")))
    (comp (ref "USB1")
      (value "918-418K2023S40001")
      (footprint "1 FEMALE USB -C 16")
      (description "USB - Type C Female 16 SMD USB Connectors RoHS")
      (libsource (lib "Connectors, Misc") (part "Female USB-C 16"))
    )
  )
  (nets
    (net (code "1") (name "/AN0-IN") (class "Default")
      (node (ref "U5") (pin "1") (pinfunction "OUT1_1") (pintype "passive"))
      (node (ref "U5") (pin "2") (pinfunction "IN1-_2") (pintype "passive"))
      (node (ref "U6") (pin "4") (pinfunction "AIN0_4") (pintype "passive"))
    )
    (net (code "2") (name "/AN0-IN-HV") (class "Default")
      (node (ref "J4") (pin "1") (pinfunction "1_1") (pintype "passive"))
      (node (ref "R20") (pin "1") (pinfunction "1_1") (pintype "passive"))
    )
    (net (code "3") (name "/AN0-OUT") (class "Default")
      (node (ref "U13") (pin "6") (pinfunction "VOUT-A_6") (pintype "passive"))
      (node (ref "U14") (pin "3") (pinfunction "IN1+_3") (pintype "passive"))
    )
    (net (code "4") (name "/AN0-OUT-HV") (class "Default")
      (node (ref "J4") (pin "2") (pinfunction "2_2") (pintype "passive"))
      (node (ref "R46") (pin "1") (pinfunction "1_1") (pintype "passive"))
      (node (ref "U14") (pin "1") (pinfunction "OUT1_1") (pintype "passive"))
    )
    (net (code "5") (name "/AN1-IN") (class "Default")
      (node (ref "U5") (pin "6") (pinfunction "IN2-_6") (pintype "passive"))
      (node (ref "U5") (pin "7") (pinfunction "OUT2_7") (pintype "passive"))
      (node (ref "U6") (pin "5") (pinfunction "AIN1_5") (pintype "passive"))
    )
    (net (code "6") (name "/AN1-IN-HV") (class "Default")
      (node (ref "J4") (pin "3") (pinfunction "3_3") (pintype "passive"))
      (node (ref "R26") (pin "1") (pinfunction "1_1") (pintype "passive"))
    )
    (net (code "7") (name "/AN1-OUT") (class "Default")
      (node (ref "U13") (pin "7") (pinfunction "VOUT-B_7") (pintype "passive"))
      (node (ref "U14") (pin "5") (pinfunction "IN2+_5") (pintype "passive"))
    )
    (net (code "8") (name "/AN1-OUT-HV") (class "Default")
      (node (ref "J4") (pin "4") (pinfunction "4_4") (pintype "passive"))
      (node (ref "R51") (pin "1") (pinfunction "1_1") (pintype "passive"))
      (node (ref "U14") (pin "7") (pinfunction "OUT2_7") (pintype "passive"))
    )
    (net (code "9") (name "/AN2-IN") (class "Default")
      (node (ref "U5") (pin "8") (pinfunction "OUT3_8") (pintype "passive"))
      (node (ref "U5") (pin "9") (pinfunction "IN3-_9") (pintype "passive"))
      (node (ref "U6") (pin "6") (pinfunction "AIN2_6") (pintype "passive"))
    )
    (net (code "10") (name "/AN2-IN-HV") (class "Default")
      (node (ref "J4") (pin "5") (pinfunction "5_5") (pintype "passive"))
      (node (ref "R30") (pin "1") (pinfunction "1_1") (pintype "passive"))
    )
    (net (code "11") (name "/AN2-OUT") (class "Default")
      (node (ref "U13") (pin "8") (pinfunction "VOUT-C_8") (pintype "passive"))
      (node (ref "U14") (pin "10") (pinfunction "IN3+_10") (pintype "passive"))
    )
    (net (code "12") (name "/AN2-OUT-HV") (class "Default")
      (node (ref "J4") (pin "6") (pinfunction "6_6") (pintype "passive"))
      (node (ref "R54") (pin "1") (pinfunction "1_1") (pintype "passive"))
      (node (ref "U14") (pin "8") (pinfunction "OUT3_8") (pintype "passive"))
    )
    (net (code "13") (name "/AN3-IN") (class "Default")
      (node (ref "U5") (pin "13") (pinfunction "IN4-_13") (pintype "passive"))
      (node (ref "U5") (pin "14") (pinfunction "OUT4_14") (pintype "passive"))
      (node (ref "U6") (pin "7") (pinfunction "AIN3_7") (pintype "passive"))
    )
    (net (code "14") (name "/AN3-IN-HV") (class "Default")
      (node (ref "J4") (pin "7") (pinfunction "7_7") (pintype "passive"))
      (node (ref "R33") (pin "1") (pinfunction "1_1") (pintype "passive"))
    )
    (net (code "15") (name "/AN3-OUT") (class "Default")
      (node (ref "U13") (pin "9") (pinfunction "VOUT-D_9") (pintype "passive"))
      (node (ref "U14") (pin "12") (pinfunction "IN4+_12") (pintype "passive"))
    )
    (net (code "16") (name "/AN3-OUT-HV") (class "Default")
      (node (ref "J4") (pin "8") (pinfunction "8_8") (pintype "passive"))
      (node (ref "R57") (pin "1") (pinfunction "1_1") (pintype "passive"))
      (node (ref "U14") (pin "14") (pinfunction "OUT4_14") (pintype "passive"))
    )
    (net (code "17") (name "/AN4-IN") (class "Default")
      (node (ref "U10") (pin "1") (pinfunction "OUT1_1") (pintype "passive"))
      (node (ref "U10") (pin "2") (pinfunction "IN1-_2") (pintype "passive"))
      (node (ref "U11") (pin "4") (pinfunction "AIN0_4") (pintype "passive"))
    )
    (net (code "18") (name "/AN5-IN") (class "Default")
      (node (ref "U10") (pin "6") (pinfunction "IN2-_6") (pintype "passive"))
      (node (ref "U10") (pin "7") (pinfunction "OUT2_7") (pintype "passive"))
      (node (ref "U11") (pin "5") (pinfunction "AIN1_5") (pintype "passive"))
    )
    (net (code "19") (name "/AN6-IN") (class "Default")
      (node (ref "U10") (pin "8") (pinfunction "OUT3_8") (pintype "passive"))
      (node (ref "U10") (pin "9") (pinfunction "IN3-_9") (pintype "passive"))
      (node (ref "U11") (pin "6") (pinfunction "AIN2_6") (pintype "passive"))
    )
    (net (code "20") (name "/AN7-IN") (class "Default")
      (node (ref "U10") (pin "13") (pinfunction "IN4-_13") (pintype "passive"))
      (node (ref "U10") (pin "14") (pinfunction "OUT4_14") (pintype "passive"))
      (node (ref "U11") (pin "7") (pinfunction "AIN3_7") (pintype "passive"))
    )
    (net (code "21") (name "/BOOT") (class "Default")
      (node (ref "SW2") (pin "2") (pintype "passive"))
      (node (ref "U2") (pin "27") (pinfunction "IO0_27") (pintype "passive"))
    )
    (net (code "22") (name "/CAN-RX") (class "Default")
      (node (ref "U1") (pin "4") (pinfunction "RXD_4") (pintype "passive"))
      (node (ref "U2") (pin "34") (pinfunction "IO41_34") (pintype "passive"))
    )
    (net (code "23") (name "/CAN-TX") (class "Default")
      (node (ref "U1") (pin "1") (pinfunction "TXD_1") (pintype "passive"))
      (node (ref "U2") (pin "33") (pinfunction "IO40_33") (pintype "passive"))
    )
    (net (code "24") (name "/EN") (class "Default")
      (node (ref "R4") (pin "1") (pinfunction "1_1") (pintype "passive"))
      (node (ref "SW1") (pin "2") (pintype "passive"))
      (node (ref "U2") (pin "3") (pinfunction "EN_3") (pintype "input"))
    )
    (net (code "25") (name "/FSPICLK") (class "Default")
      (node (ref "J2") (pin "3") (pinfunction "3_3") (pintype "passive"))
      (node (ref "U2") (pin "20") (pinfunction "IO12_20") (pintype "passive"))
    )
    (net (code "26") (name "/FSPICS0") (class "Default")
      (node (ref "J2") (pin "1") (pinfunction "1_1") (pintype "passive"))
      (node (ref "U2") (pin "18") (pinfunction "IO10_18") (pintype "passive"))
    )
    (net (code "27") (name "/FSPID") (class "Default")
      (node (ref "J2") (pin "4") (pinfunction "4_4") (pintype "passive"))
      (node (ref "U2") (pin "19") (pinfunction "IO11_19") (pintype "passive"))
    )
    (net (code "28") (name "/FSPIHD") (class "Default")
      (node (ref "J2") (pin "2") (pinfunction "2_2") (pintype "passive"))
      (node (ref "U2") (pin "17") (pinfunction "IO9_17") (pintype "passive"))
    )
    (net (code "29") (name "/FSPIQ") (class "Default")
      (node (ref "J2") (pin "6") (pinfunction "6_6") (pintype "passive"))
      (node (ref "U2") (pin "21") (pinfunction "IO13_21") (pintype "passive"))
    )
    (net (code "30") (name "/FSPIWP") (class "Default")
      (node (ref "J2") (pin "5") (pinfunction "5_5") (pintype "passive"))
      (node (ref "U2") (pin "22") (pinfunction "IO14_22") (pintype "passive"))
    )
    (net (code "31") (name "/I2C0-SCL") (class "Default")
      (node (ref "R13") (pin "1") (pinfunction "1_1") (pintype "passive"))
      (node (ref "U11") (pin "10") (pinfunction "SCL_10") (pintype "passive"))
      (node (ref "U12") (pin "5") (pinfunction "SCL_5") (pintype "passive"))
      (node (ref "U13") (pin "2") (pinfunction "SCL_2") (pintype "passive"))
      (node (ref "U15") (pin "5") (pinfunction "SCL_5") (pintype "passive"))
      (node (ref "U2") (pin "15") (pinfunction "IO3_15") (pintype "passive"))
      (node (ref "U6") (pin "10") (pinfunction "SCL_10") (pintype "passive"))
    )
    (net (code "32") (name "/I2C0-SDA") (class "Default")
      (node (ref "R12") (pin "1") (pinfunction "1_1") (pintype "passive"))
      (node (ref "U11") (pin "9") (pinfunction "SDA_9") (pintype "passive"))
      (node (ref "U12") (pin "4") (pinfunction "SDA_4") (pintype "passive"))
      (node (ref "U13") (pin "3") (pinfunction "SDA_3") (pintype "passive"))
      (node (ref "U15") (pin "4") (pinfunction "SDA_4") (pintype "passive"))
      (node (ref "U2") (pin "16") (pinfunction "IO46_16") (pintype "passive"))
      (node (ref "U6") (pin "9") (pinfunction "SDA_9") (pintype "passive"))
    )
    (net (code "33") (name "/I2C1-SCL") (class "Default")
      (node (ref "R15") (pin "1") (pinfunction "1_1") (pintype "passive"))
      (node (ref "U2") (pin "38") (pinfunction "IO2_38") (pintype "passive"))
    )
    (net (code "34") (name "/I2C1-SDA") (class "Default")
      (node (ref "R14") (pin "1") (pinfunction "1_1") (pintype "passive"))
      (node (ref "U2") (pin "39") (pinfunction "IO1_39") (pintype "passive"))
    )
    (net (code "35") (name "/IO-0") (class "Default")
      (node (ref "R11") (pin "1") (pinfunction "1_1") (pintype "passive"))
      (node (ref "U2") (pin "4") (pinfunction "IO4_4") (pintype "passive"))
    )
    (net (code "36") (name "/IO-1") (class "Default")
      (node (ref "R10") (pin "1") (pinfunction "1_1") (pintype "passive"))
      (node (ref "U2") (pin "5") (pinfunction "IO5_5") (pintype "passive"))
    )
    (net (code "37") (name "/IO-2") (class "Default")
      (node (ref "R9") (pin "1") (pinfunction "1_1") (pintype "passive"))
      (node (ref "U2") (pin "6") (pinfunction "IO6_6") (pintype "passive"))
    )
    (net (code "38") (name "/IO-3") (class "Default")
      (node (ref "R8") (pin "1") (pinfunction "1_1") (pintype "passive"))
      (node (ref "U2") (pin "7") (pinfunction "IO7_7") (pintype "passive"))
    )
    (net (code "39") (name "/IO-4") (class "Default")
      (node (ref "R6") (pin "1") (pinfunction "1_1") (pintype "passive"))
      (node (ref "U2") (pin "8") (pinfunction "IO15_8") (pintype "passive"))
    )
    (net (code "40") (name "/IO-5") (class "Default")
      (node (ref "R5") (pin "1") (pinfunction "1_1") (pintype "passive"))
      (node (ref "U2") (pin "9") (pinfunction "IO16_9") (pintype "passive"))
    )
    (net (code "41") (name "/IO-6") (class "Default")
      (node (ref "R2") (pin "1") (pinfunction "1_1") (pintype "passive"))
      (node (ref "U2") (pin "10") (pinfunction "IO17_10") (pintype "passive"))
    )
    (net (code "42") (name "/IO-7") (class "Default")
      (node (ref "R1") (pin "1") (pinfunction "1_1") (pintype "passive"))
      (node (ref "U2") (pin "11") (pinfunction "IO18_11") (pintype "passive"))
    )
    (net (code "43") (name "/LED") (class "Default")
      (node (ref "U2") (pin "26") (pinfunction "IO45_26") (pintype "passive"))
      (node (ref "U3") (pin "3") (pinfunction "DI_3") (pintype "input"))
    )
    (net (code "44") (name "/NTC0") (class "Default")
      (node (ref "C14") (pin "2") (pinfunction "2_2") (pintype "passive"))
      (node (ref "J6") (pin "2") (pinfunction "2_2") (pintype "passive"))
      (node (ref "R36") (pin "1") (pinfunction "1_1") (pintype "passive"))
      (node (ref "U10") (pin "3") (pinfunction "IN1+_3") (pintype "passive"))
    )
    (net (code "45") (name "/NTC1") (class "Default")
      (node (ref "C15") (pin "2") (pinfunction "2_2") (pintype "passive"))
      (node (ref "J7") (pin "2") (pinfunction "2_2") (pintype "passive"))
      (node (ref "R37") (pin "1") (pinfunction "1_1") (pintype "passive"))
      (node (ref "U10") (pin "5") (pinfunction "IN2+_5") (pintype "passive"))
    )
    (net (code "46") (name "/PowerCtrl0") (class "Default")
      (node (ref "Q4") (pin "1") (pinfunction "G_1") (pintype "passive"))
      (node (ref "R50") (pin "1") (pinfunction "1_1") (pintype "passive"))
      (node (ref "U2") (pin "31") (pinfunction "IO38_31") (pintype "passive"))
    )
    (net (code "47") (name "/PowerCtrl1") (class "Default")
      (node (ref "Q2") (pin "1") (pinfunction "G_1") (pintype "passive"))
      (node (ref "R42") (pin "1") (pinfunction "1_1") (pintype "passive"))
      (node (ref "U2") (pin "32") (pinfunction "IO39_32") (pintype "passive"))
    )
    (net (code "48") (name "/RS485") (class "Default")
      (node (ref "R18") (pin "2") (pinfunction "2_2") (pintype "passive"))
      (node (ref "U2") (pin "35") (pinfunction "IO42_35") (pintype "passive"))
    )
    (net (code "49") (name "/UART0-RX") (class "Default")
      (node (ref "U2") (pin "36") (pinfunction "RXD0_36") (pintype "passive"))
      (node (ref "U4") (pin "1") (pinfunction "RO_1") (pintype "passive"))
    )
    (net (code "50") (name "/UART0-TX") (class "Default")
      (node (ref "U2") (pin "37") (pinfunction "TXD0_37") (pintype "passive"))
      (node (ref "U4") (pin "4") (pinfunction "DI_4") (pintype "passive"))
    )
    (net (code "51") (name "/USB_N") (class "Default")
      (node (ref "U2") (pin "13") (pinfunction "IO19_13") (pintype "passive"))
      (node (ref "USB1") (pin "A7") (pinfunction "DN1_A7") (pintype "passive"))
      (node (ref "USB1") (pin "B7") (pinfunction "DN2_B7") (pintype "passive"))
    )
    (net (code "52") (name "/USB_P") (class "Default")
      (node (ref "U2") (pin "14") (pinfunction "IO20_14") (pintype "passive"))
      (node (ref "USB1") (pin "A6") (pinfunction "DP1_A6") (pintype "passive"))
      (node (ref "USB1") (pin "B6") (pinfunction "DP2_B6") (pintype "passive"))
    )
    (net (code "53") (name "3V3") (class "Default")
      (node (ref "C1") (pin "2") (pinfunction "2_2") (pintype "passive"))
      (node (ref "C10") (pin "2") (pinfunction "2_2") (pintype "passive"))
      (node (ref "C2") (pin "2") (pinfunction "2_2") (pintype "passive"))
      (node (ref "C3") (pin "2") (pinfunction "2_2") (pintype "passive"))
      (node (ref "C4") (pin "2") (pinfunction "2_2") (pintype "passive"))
      (node (ref "J2") (pin "10") (pinfunction "10_10") (pintype "passive"))
      (node (ref "R12") (pin "2") (pinfunction "2_2") (pintype "passive"))
      (node (ref "R13") (pin "2") (pinfunction "2_2") (pintype "passive"))
      (node (ref "R14") (pin "2") (pinfunction "2_2") (pintype "passive"))
      (node (ref "R15") (pin "2") (pinfunction "2_2") (pintype "passive"))
      (node (ref "R16") (pin "2") (pinfunction "2_2") (pintype "passive"))
      (node (ref "R4") (pin "2") (pinfunction "2_2") (pintype "passive"))
      (node (ref "TP3") (pin "1") (pinfunction "1_1") (pintype "passive"))
      (node (ref "U1") (pin "3") (pinfunction "VCC_3") (pintype "passive"))
      (node (ref "U2") (pin "2") (pinfunction "3V3_2") (pintype "passive"))
      (node (ref "U4") (pin "8") (pinfunction "VCC_8") (pintype "passive"))
      (node (ref "U8") (pin "2") (pinfunction "OUT_2") (pintype "passive"))
    )
    (net (code "54") (name "3V3-ANALOG") (class "Default")
      (node (ref "C12") (pin "2") (pinfunction "2_2") (pintype "passive"))
      (node (ref "C16") (pin "2") (pinfunction "2_2") (pintype "passive"))
      (node (ref "C20") (pin "2") (pinfunction "2_2") (pintype "passive"))
      (node (ref "C23") (pin "2") (pinfunction "2_2") (pintype "passive"))
      (node (ref "C25") (pin "2") (pinfunction "2_2") (pintype "passive"))
      (node (ref "C7") (pin "2") (pinfunction "2_2") (pintype "passive"))
      (node (ref "J6") (pin "1") (pinfunction "1_1") (pintype "passive"))
      (node (ref "J7") (pin "1") (pinfunction "1_1") (pintype "passive"))
      (node (ref "TP4") (pin "1") (pinfunction "1_1") (pintype "passive"))
      (node (ref "U11") (pin "1") (pinfunction "ADDR_1") (pintype "passive"))
      (node (ref "U11") (pin "8") (pinfunction "VDD_8") (pintype "passive"))
      (node (ref "U12") (pin "6") (pinfunction "VS_6") (pintype "passive"))
      (node (ref "U13") (pin "1") (pinfunction "VDD_1") (pintype "passive"))
      (node (ref "U15") (pin "1") (pinfunction "A1_1") (pintype "passive"))
      (node (ref "U15") (pin "2") (pinfunction "A0_2") (pintype "passive"))
      (node (ref "U15") (pin "6") (pinfunction "VS_6") (pintype "passive"))
      (node (ref "U6") (pin "8") (pinfunction "VDD_8") (pintype "passive"))
      (node (ref "U9") (pin "2") (pinfunction "OUT_2") (pintype "passive"))
    )
    (net (code "55") (name "GND") (class "Default")
      (node (ref "C1") (pin "1") (pinfunction "1_1") (pintype "passive"))
      (node (ref "C10") (pin "1") (pinfunction "1_1") (pintype "passive"))
      (node (ref "C11") (pin "1") (pinfunction "1_1") (pintype "passive"))
      (node (ref "C12") (pin "1") (pinfunction "1_1") (pintype "passive"))
      (node (ref "C13") (pin "1") (pinfunction "1_1") (pintype "passive"))
      (node (ref "C14") (pin "1") (pinfunction "1_1") (pintype "passive"))
      (node (ref "C15") (pin "1") (pinfunction "1_1") (pintype "passive"))
      (node (ref "C16") (pin "1") (pinfunction "1_1") (pintype "passive"))
      (node (ref "C17") (pin "2") (pinfunction "2_2") (pintype "passive"))
      (node (ref "C18") (pin "1") (pinfunction "1_1") (pintype "passive"))
      (node (ref "C19") (pin "1") (pinfunction "1_1") (pintype "passive"))
      (node (ref "C2") (pin "1") (pinfunction "1_1") (pintype "passive"))
      (node (ref "C20") (pin "1") (pinfunction "1_1") (pintype "passive"))
      (node (ref "C21") (pin "1") (pinfunction "1_1") (pintype "passive"))
      (node (ref "C22") (pin "2") (pinfunction "2_2") (pintype "passive"))
      (node (ref "C23") (pin "1") (pinfunction "1_1") (pintype "passive"))
      (node (ref "C24") (pin "1") (pinfunction "1_1") (pintype "passive"))
      (node (ref "C25") (pin "1") (pinfunction "1_1") (pintype "passive"))
      (node (ref "C3") (pin "1") (pinfunction "1_1") (pintype "passive"))
      (node (ref "C4") (pin "1") (pinfunction "1_1") (pintype "passive"))
      (node (ref "C5") (pin "1") (pinfunction "1_1") (pintype "passive"))
      (node (ref "C6") (pin "1") (pinfunction "1_1") (pintype "passive"))
      (node (ref "C7") (pin "1") (pinfunction "1_1") (pintype "passive"))
      (node (ref "C8") (pin "1") (pinfunction "1_1") (pintype "passive"))
      (node (ref "C9") (pin "1") (pinfunction "1_1") (pintype "passive"))
      (node (ref "D1") (pin "2") (pintype "passive"))
      (node (ref "D2") (pin "2") (pintype "passive"))
      (node (ref "D3") (pin "2") (pintype "passive"))
      (node (ref "D4") (pin "1") (pintype "passive"))
      (node (ref "J10") (pin "2") (pinfunction "2_2") (pintype "passive"))
      (node (ref "J2") (pin "7") (pinfunction "7_7") (pintype "passive"))
      (node (ref "J2") (pin "9") (pinfunction "9_9") (pintype "passive"))
      (node (ref "J3") (pin "10") (pinfunction "10_10") (pintype "passive"))
      (node (ref "J3") (pin "9") (pinfunction "9_9") (pintype "passive"))
      (node (ref "J4") (pin "10") (pinfunction "10_10") (pintype "passive"))
      (node (ref "J4") (pin "9") (pinfunction "9_9") (pintype "passive"))
      (node (ref "J6") (pin "0") (pinfunction "G_0") (pintype "passive"))
      (node (ref "J7") (pin "0") (pinfunction "G_0") (pintype "passive"))
      (node (ref "J8") (pin "2") (pinfunction "2_2") (pintype "passive"))
      (node (ref "J9") (pin "2") (pinfunction "TN_2") (pintype "passive"))
      (node (ref "Q2") (pin "2") (pinfunction "S_2") (pintype "passive"))
      (node (ref "Q4") (pin "2") (pinfunction "S_2") (pintype "passive"))
      (node (ref "R19") (pin "1") (pinfunction "1_1") (pintype "passive"))
      (node (ref "R23") (pin "2") (pinfunction "2_2") (pintype "passive"))
      (node (ref "R24") (pin "1") (pinfunction "1_1") (pintype "passive"))
      (node (ref "R25") (pin "2") (pinfunction "2_2") (pintype "passive"))
      (node (ref "R28") (pin "1") (pinfunction "1_1") (pintype "passive"))
      (node (ref "R29") (pin "2") (pinfunction "2_2") (pintype "passive"))
      (node (ref "R32") (pin "2") (pinfunction "2_2") (pintype "passive"))
      (node (ref "R35") (pin "2") (pinfunction "2_2") (pintype "passive"))
      (node (ref "R36") (pin "2") (pinfunction "2_2") (pintype "passive"))
      (node (ref "R37") (pin "2") (pinfunction "2_2") (pintype "passive"))
      (node (ref "R40") (pin "2") (pinfunction "2_2") (pintype "passive"))
      (node (ref "R42") (pin "2") (pinfunction "2_2") (pintype "passive"))
      (node (ref "R43") (pin "2") (pinfunction "2_2") (pintype "passive"))
      (node (ref "R49") (pin "1") (pinfunction "1_1") (pintype "passive"))
      (node (ref "R50") (pin "2") (pinfunction "2_2") (pintype "passive"))
      (node (ref "R53") (pin "1") (pinfunction "1_1") (pintype "passive"))
      (node (ref "R56") (pin "1") (pinfunction "1_1") (pintype "passive"))
      (node (ref "R59") (pin "1") (pinfunction "1_1") (pintype "passive"))
      (node (ref "R7") (pin "2") (pinfunction "2_2") (pintype "passive"))
      (node (ref "SW1") (pin "1") (pintype "passive"))
      (node (ref "SW2") (pin "1") (pintype "passive"))
      (node (ref "U1") (pin "2") (pinfunction "GND_2") (pintype "passive"))
      (node (ref "U10") (pin "11") (pinfunction "VCC-_11") (pintype "passive"))
      (node (ref "U11") (pin "3") (pinfunction "GND_3") (pintype "passive"))
      (node (ref "U12") (pin "1") (pinfunction "A1_1") (pintype "passive"))
      (node (ref "U12") (pin "2") (pinfunction "A0_2") (pintype "passive"))
      (node (ref "U12") (pin "7") (pinfunction "GND_7") (pintype "passive"))
      (node (ref "U13") (pin "10") (pinfunction "VSS_10") (pintype "passive"))
      (node (ref "U13") (pin "4") (pinfunction "~{LDAC}_4") (pintype "passive"))
      (node (ref "U14") (pin "11") (pinfunction "VCC-_11") (pintype "passive"))
      (node (ref "U15") (pin "7") (pinfunction "GND_7") (pintype "passive"))
      (node (ref "U2") (pin "0") (pinfunction "PAD_0") (pintype "passive"))
      (node (ref "U2") (pin "1") (pinfunction "GND_1") (pintype "passive"))
      (node (ref "U2") (pin "40") (pinfunction "GND_40") (pintype "passive"))
      (node (ref "U3") (pin "2") (pinfunction "GND_2") (pintype "passive"))
      (node (ref "U4") (pin "5") (pinfunction "GND_5") (pintype "passive"))
      (node (ref "U5") (pin "11") (pinfunction "VCC-_11") (pintype "passive"))
      (node (ref "U6") (pin "1") (pinfunction "ADDR_1") (pintype "passive"))
      (node (ref "U6") (pin "3") (pinfunction "GND_3") (pintype "passive"))
      (node (ref "U7") (pin "2") (pinfunction "GND_2") (pintype "passive"))
      (node (ref "U8") (pin "1") (pinfunction "GND/ADJ_1") (pintype "passive"))
      (node (ref "U9") (pin "1") (pinfunction "GND/ADJ_1") (pintype "passive"))
      (node (ref "USB1") (pin "A12_-_B1") (pinfunction "GND_A12_-_B1") (pintype "passive"))
      (node (ref "USB1") (pin "A1_-_B12") (pinfunction "GND_A1_-_B12") (pintype "passive"))
      (node (ref "USB1") (pin "Shell") (pinfunction "Shield_Shell") (pintype "passive"))
    )
    (net (code "56") (name "Net-(D5-Anode)") (class "Default")
      (node (ref "D5") (pin "2") (pinfunction "Anode_2") (pintype "passive"))
      (node (ref "L1") (pin "1") (pinfunction "1_1") (pintype "passive"))
      (node (ref "U7") (pin "1") (pinfunction "SW_1") (pintype "passive"))
    )
    (net (code "57") (name "Net-(D5-Cathode)") (class "Default")
      (node (ref "D5") (pin "1") (pinfunction "Cathode_1") (pintype "passive"))
      (node (ref "FB2") (pin "1") (pintype "passive"))
      (node (ref "R22") (pin "2") (pinfunction "2_2") (pintype "passive"))
    )
    (net (code "58") (name "Net-(FB1-Pad2)") (class "Default")
      (node (ref "FB1") (pin "2") (pintype "passive"))
      (node (ref "USB1") (pin "A4_-_B9") (pinfunction "VBUS_A4_-_B9") (pintype "passive"))
      (node (ref "USB1") (pin "A9_-_B4") (pinfunction "VBUS_A9_-_B4") (pintype "passive"))
    )
    (net (code "59") (name "Net-(J3-Pad1)") (class "Default")
      (node (ref "J3") (pin "1") (pinfunction "1_1") (pintype "passive"))
      (node (ref "R1") (pin "2") (pinfunction "2_2") (pintype "passive"))
    )
    (net (code "60") (name "Net-(J3-Pad2)") (class "Default")
      (node (ref "J3") (pin "2") (pinfunction "2_2") (pintype "passive"))
      (node (ref "R2") (pin "2") (pinfunction "2_2") (pintype "passive"))
    )
    (net (code "61") (name "Net-(J3-Pad3)") (class "Default")
      (node (ref "J3") (pin "3") (pinfunction "3_3") (pintype "passive"))
      (node (ref "R5") (pin "2") (pinfunction "2_2") (pintype "passive"))
    )
    (net (code "62") (name "Net-(J3-Pad4)") (class "Default")
      (node (ref "J3") (pin "4") (pinfunction "4_4") (pintype "passive"))
      (node (ref "R6") (pin "2") (pinfunction "2_2") (pintype "passive"))
    )
    (net (code "63") (name "Net-(J3-Pad5)") (class "Default")
      (node (ref "J3") (pin "5") (pinfunction "5_5") (pintype "passive"))
      (node (ref "R8") (pin "2") (pinfunction "2_2") (pintype "passive"))
    )
    (net (code "64") (name "Net-(J3-Pad6)") (class "Default")
      (node (ref "J3") (pin "6") (pinfunction "6_6") (pintype "passive"))
      (node (ref "R9") (pin "2") (pinfunction "2_2") (pintype "passive"))
    )
    (net (code "65") (name "Net-(J3-Pad7)") (class "Default")
      (node (ref "J3") (pin "7") (pinfunction "7_7") (pintype "passive"))
      (node (ref "R10") (pin "2") (pinfunction "2_2") (pintype "passive"))
    )
    (net (code "66") (name "Net-(J3-Pad8)") (class "Default")
      (node (ref "J3") (pin "8") (pinfunction "8_8") (pintype "passive"))
      (node (ref "R11") (pin "2") (pinfunction "2_2") (pintype "passive"))
    )
    (net (code "67") (name "Net-(J9-T)") (class "Default")
      (node (ref "FB3") (pin "1") (pintype "passive"))
      (node (ref "J9") (pin "1") (pinfunction "T_1") (pintype "passive"))
    )
    (net (code "68") (name "Net-(Q1-D)") (class "Default")
      (node (ref "Q1") (pin "3") (pinfunction "D_3") (pintype "passive"))
      (node (ref "R38") (pin "1") (pinfunction "1_1") (pintype "passive"))
      (node (ref "U12") (pin "10") (pinfunction "IN+_10") (pintype "passive"))
      (node (ref "U12") (pin "8") (pinfunction "VBUS_8") (pintype "passive"))
    )
    (net (code "69") (name "Net-(Q1-G)") (class "Default")
      (node (ref "Q1") (pin "1") (pinfunction "G_1") (pintype "passive"))
      (node (ref "Q2") (pin "3") (pinfunction "D_3") (pintype "passive"))
      (node (ref "R41") (pin "2") (pinfunction "2_2") (pintype "passive"))
    )
    (net (code "70") (name "Net-(Q3-D)") (class "Default")
      (node (ref "Q3") (pin "3") (pinfunction "D_3") (pintype "passive"))
      (node (ref "R45") (pin "1") (pinfunction "1_1") (pintype "passive"))
      (node (ref "U15") (pin "10") (pinfunction "IN+_10") (pintype "passive"))
      (node (ref "U15") (pin "8") (pinfunction "VBUS_8") (pintype "passive"))
    )
    (net (code "71") (name "Net-(Q3-G)") (class "Default")
      (node (ref "Q3") (pin "1") (pinfunction "G_1") (pintype "passive"))
      (node (ref "Q4") (pin "3") (pinfunction "D_3") (pintype "passive"))
      (node (ref "R48") (pin "2") (pinfunction "2_2") (pintype "passive"))
    )
    (net (code "72") (name "Net-(R20-Pad2)") (class "Default")
      (node (ref "R20") (pin "2") (pinfunction "2_2") (pintype "passive"))
      (node (ref "R21") (pin "1") (pinfunction "1_1") (pintype "passive"))
    )
    (net (code "73") (name "Net-(R26-Pad2)") (class "Default")
      (node (ref "R26") (pin "2") (pinfunction "2_2") (pintype "passive"))
      (node (ref "R27") (pin "1") (pinfunction "1_1") (pintype "passive"))
    )
    (net (code "74") (name "Net-(R30-Pad2)") (class "Default")
      (node (ref "R30") (pin "2") (pinfunction "2_2") (pintype "passive"))
      (node (ref "R31") (pin "1") (pinfunction "1_1") (pintype "passive"))
    )
    (net (code "75") (name "Net-(R33-Pad2)") (class "Default")
      (node (ref "R33") (pin "2") (pinfunction "2_2") (pintype "passive"))
      (node (ref "R34") (pin "1") (pinfunction "1_1") (pintype "passive"))
    )
    (net (code "76") (name "Net-(R46-Pad2)") (class "Default")
      (node (ref "R46") (pin "2") (pinfunction "2_2") (pintype "passive"))
      (node (ref "R47") (pin "1") (pinfunction "1_1") (pintype "passive"))
    )
    (net (code "77") (name "Net-(R51-Pad2)") (class "Default")
      (node (ref "R51") (pin "2") (pinfunction "2_2") (pintype "passive"))
      (node (ref "R52") (pin "1") (pinfunction "1_1") (pintype "passive"))
    )
    (net (code "78") (name "Net-(R54-Pad2)") (class "Default")
      (node (ref "R54") (pin "2") (pinfunction "2_2") (pintype "passive"))
      (node (ref "R55") (pin "1") (pinfunction "1_1") (pintype "passive"))
    )
    (net (code "79") (name "Net-(R57-Pad2)") (class "Default")
      (node (ref "R57") (pin "2") (pinfunction "2_2") (pintype "passive"))
      (node (ref "R58") (pin "1") (pinfunction "1_1") (pintype "passive"))
    )
    (net (code "80") (name "Net-(U1-CANH)") (class "Default")
      (node (ref "D1") (pin "1") (pintype "passive"))
      (node (ref "J1") (pin "2") (pinfunction "2_2") (pintype "passive"))
      (node (ref "R3") (pin "2") (pinfunction "2_2") (pintype "passive"))
      (node (ref "U1") (pin "7") (pinfunction "CANH_7") (pintype "passive"))
    )
    (net (code "81") (name "Net-(U1-CANL)") (class "Default")
      (node (ref "D2") (pin "1") (pintype "passive"))
      (node (ref "J1") (pin "1") (pinfunction "1_1") (pintype "passive"))
      (node (ref "R3") (pin "1") (pinfunction "1_1") (pintype "passive"))
      (node (ref "U1") (pin "6") (pinfunction "CANL_6") (pintype "passive"))
    )
    (net (code "82") (name "Net-(U1-RS)") (class "Default")
      (node (ref "R7") (pin "1") (pinfunction "1_1") (pintype "passive"))
      (node (ref "U1") (pin "8") (pinfunction "RS_8") (pintype "passive"))
    )
    (net (code "83") (name "Net-(U4-A)") (class "Default")
      (node (ref "D3") (pin "1") (pintype "passive"))
      (node (ref "J5") (pin "2") (pinfunction "2_2") (pintype "passive"))
      (node (ref "R16") (pin "1") (pinfunction "1_1") (pintype "passive"))
      (node (ref "R17") (pin "2") (pinfunction "2_2") (pintype "passive"))
      (node (ref "U4") (pin "6") (pinfunction "A_6") (pintype "passive"))
    )
    (net (code "84") (name "Net-(U4-B)") (class "Default")
      (node (ref "D4") (pin "2") (pintype "passive"))
      (node (ref "J5") (pin "1") (pinfunction "1_1") (pintype "passive"))
      (node (ref "R17") (pin "1") (pinfunction "1_1") (pintype "passive"))
      (node (ref "R19") (pin "2") (pinfunction "2_2") (pintype "passive"))
      (node (ref "U4") (pin "7") (pinfunction "B_7") (pintype "passive"))
    )
    (net (code "85") (name "Net-(U4-DE)") (class "Default")
      (node (ref "R18") (pin "1") (pinfunction "1_1") (pintype "passive"))
      (node (ref "U4") (pin "2") (pinfunction "~{RE}_2") (pintype "passive"))
      (node (ref "U4") (pin "3") (pinfunction "DE_3") (pintype "passive"))
    )
    (net (code "86") (name "Net-(U5-IN1+)") (class "Default")
      (node (ref "R21") (pin "2") (pinfunction "2_2") (pintype "passive"))
      (node (ref "R25") (pin "1") (pinfunction "1_1") (pintype "passive"))
      (node (ref "U5") (pin "3") (pinfunction "IN1+_3") (pintype "passive"))
    )
    (net (code "87") (name "Net-(U5-IN2+)") (class "Default")
      (node (ref "R27") (pin "2") (pinfunction "2_2") (pintype "passive"))
      (node (ref "R29") (pin "1") (pinfunction "1_1") (pintype "passive"))
      (node (ref "U5") (pin "5") (pinfunction "IN2+_5") (pintype "passive"))
    )
    (net (code "88") (name "Net-(U5-IN3+)") (class "Default")
      (node (ref "R31") (pin "2") (pinfunction "2_2") (pintype "passive"))
      (node (ref "R32") (pin "1") (pinfunction "1_1") (pintype "passive"))
      (node (ref "U5") (pin "10") (pinfunction "IN3+_10") (pintype "passive"))
    )
    (net (code "89") (name "Net-(U5-IN4+)") (class "Default")
      (node (ref "R34") (pin "2") (pinfunction "2_2") (pintype "passive"))
      (node (ref "R35") (pin "1") (pinfunction "1_1") (pintype "passive"))
      (node (ref "U5") (pin "12") (pinfunction "IN4+_12") (pintype "passive"))
    )
    (net (code "90") (name "Net-(U7-FB)") (class "Default")
      (node (ref "R22") (pin "1") (pinfunction "1_1") (pintype "passive"))
      (node (ref "R28") (pin "2") (pinfunction "2_2") (pintype "passive"))
      (node (ref "U7") (pin "3") (pinfunction "FB_3") (pintype "passive"))
    )
    (net (code "91") (name "Net-(U10-IN3+)") (class "Default")
      (node (ref "C18") (pin "2") (pinfunction "2_2") (pintype "passive"))
      (node (ref "R39") (pin "2") (pinfunction "2_2") (pintype "passive"))
      (node (ref "R40") (pin "1") (pinfunction "1_1") (pintype "passive"))
      (node (ref "U10") (pin "10") (pinfunction "IN3+_10") (pintype "passive"))
    )
    (net (code "92") (name "Net-(U10-IN4+)") (class "Default")
      (node (ref "C19") (pin "2") (pinfunction "2_2") (pintype "passive"))
      (node (ref "R43") (pin "1") (pinfunction "1_1") (pintype "passive"))
      (node (ref "R44") (pin "2") (pinfunction "2_2") (pintype "passive"))
      (node (ref "U10") (pin "12") (pinfunction "IN4+_12") (pintype "passive"))
    )
    (net (code "93") (name "Net-(U12-IN-)") (class "Default")
      (node (ref "C17") (pin "1") (pinfunction "1_1") (pintype "passive"))
      (node (ref "J8") (pin "1") (pinfunction "1_1") (pintype "passive"))
      (node (ref "R38") (pin "2") (pinfunction "2_2") (pintype "passive"))
      (node (ref "U12") (pin "9") (pinfunction "IN-_9") (pintype "passive"))
    )
    (net (code "94") (name "Net-(U14-IN1-)") (class "Default")
      (node (ref "R47") (pin "2") (pinfunction "2_2") (pintype "passive"))
      (node (ref "R49") (pin "2") (pinfunction "2_2") (pintype "passive"))
      (node (ref "U14") (pin "2") (pinfunction "IN1-_2") (pintype "passive"))
    )
    (net (code "95") (name "Net-(U14-IN2-)") (class "Default")
      (node (ref "R52") (pin "2") (pinfunction "2_2") (pintype "passive"))
      (node (ref "R53") (pin "2") (pinfunction "2_2") (pintype "passive"))
      (node (ref "U14") (pin "6") (pinfunction "IN2-_6") (pintype "passive"))
    )
    (net (code "96") (name "Net-(U14-IN3-)") (class "Default")
      (node (ref "R55") (pin "2") (pinfunction "2_2") (pintype "passive"))
      (node (ref "R56") (pin "2") (pinfunction "2_2") (pintype "passive"))
      (node (ref "U14") (pin "9") (pinfunction "IN3-_9") (pintype "passive"))
    )
    (net (code "97") (name "Net-(U14-IN4-)") (class "Default")
      (node (ref "R58") (pin "2") (pinfunction "2_2") (pintype "passive"))
      (node (ref "R59") (pin "2") (pinfunction "2_2") (pintype "passive"))
      (node (ref "U14") (pin "13") (pinfunction "IN4-_13") (pintype "passive"))
    )
    (net (code "98") (name "Net-(U15-IN-)") (class "Default")
      (node (ref "C22") (pin "1") (pinfunction "1_1") (pintype "passive"))
      (node (ref "J10") (pin "1") (pinfunction "1_1") (pintype "passive"))
      (node (ref "R45") (pin "2") (pinfunction "2_2") (pintype "passive"))
      (node (ref "U15") (pin "9") (pinfunction "IN-_9") (pintype "passive"))
    )
    (net (code "99") (name "Net-(USB1-CC1)") (class "Default")
      (node (ref "R24") (pin "2") (pinfunction "2_2") (pintype "passive"))
      (node (ref "USB1") (pin "A5") (pinfunction "CC1_A5") (pintype "passive"))
    )
    (net (code "100") (name "Net-(USB1-CC2)") (class "Default")
      (node (ref "R23") (pin "1") (pinfunction "1_1") (pintype "passive"))
      (node (ref "USB1") (pin "B5") (pinfunction "CC2_B5") (pintype "passive"))
    )
    (net (code "101") (name "VBOOST") (class "Default")
      (node (ref "C21") (pin "2") (pinfunction "2_2") (pintype "passive"))
      (node (ref "C8") (pin "2") (pinfunction "2_2") (pintype "passive"))
      (node (ref "FB2") (pin "2") (pintype "passive"))
      (node (ref "TP2") (pin "1") (pinfunction "1_1") (pintype "passive"))
      (node (ref "U14") (pin "4") (pinfunction "VCC+_4") (pintype "passive"))
    )
    (net (code "102") (name "VBUS") (class "Default")
      (node (ref "C11") (pin "2") (pinfunction "2_2") (pintype "passive"))
      (node (ref "C13") (pin "2") (pinfunction "2_2") (pintype "passive"))
      (node (ref "C24") (pin "2") (pinfunction "2_2") (pintype "passive"))
      (node (ref "C5") (pin "2") (pinfunction "2_2") (pintype "passive"))
      (node (ref "C6") (pin "2") (pinfunction "2_2") (pintype "passive"))
      (node (ref "C9") (pin "2") (pinfunction "2_2") (pintype "passive"))
      (node (ref "FB1") (pin "1") (pintype "passive"))
      (node (ref "J2") (pin "8") (pinfunction "8_8") (pintype "passive"))
      (node (ref "L1") (pin "2") (pinfunction "2_2") (pintype "passive"))
      (node (ref "Q3") (pin "2") (pinfunction "S_2") (pintype "passive"))
      (node (ref "R44") (pin "1") (pinfunction "1_1") (pintype "passive"))
      (node (ref "R48") (pin "1") (pinfunction "1_1") (pintype "passive"))
      (node (ref "TP1") (pin "1") (pinfunction "1_1") (pintype "passive"))
      (node (ref "U10") (pin "4") (pinfunction "VCC+_4") (pintype "passive"))
      (node (ref "U3") (pin "4") (pinfunction "VDD_4") (pintype "passive"))
      (node (ref "U5") (pin "4") (pinfunction "VCC+_4") (pintype "passive"))
      (node (ref "U7") (pin "4") (pinfunction "EN_4") (pintype "passive"))
      (node (ref "U7") (pin "5") (pinfunction "IN_5") (pintype "passive"))
      (node (ref "U8") (pin "3") (pinfunction "IN_3") (pintype "passive"))
      (node (ref "U9") (pin "3") (pinfunction "IN_3") (pintype "passive"))
    )
    (net (code "103") (name "VDC") (class "Default")
      (node (ref "FB3") (pin "2") (pintype "passive"))
      (node (ref "Q1") (pin "2") (pinfunction "S_2") (pintype "passive"))
      (node (ref "R39") (pin "1") (pinfunction "1_1") (pintype "passive"))
      (node (ref "R41") (pin "1") (pinfunction "1_1") (pintype "passive"))
    )
    (net (code "104") (name "unconnected-(J9-S-Pad3)") (class "Default")
      (node (ref "J9") (pin "3") (pinfunction "S_3") (pintype "power_in"))
    )
    (net (code "105") (name "unconnected-(U1-Vref-Pad5)") (class "Default")
      (node (ref "U1") (pin "5") (pinfunction "Vref_5") (pintype "passive"))
    )
    (net (code "106") (name "unconnected-(U2-IO8-Pad12)") (class "Default")
      (node (ref "U2") (pin "12") (pinfunction "IO8_12") (pintype "passive"))
    )
    (net (code "107") (name "unconnected-(U2-IO21-Pad23)") (class "Default")
      (node (ref "U2") (pin "23") (pinfunction "IO21_23") (pintype "passive"))
    )
    (net (code "108") (name "unconnected-(U2-IO35-Pad28)") (class "Default")
      (node (ref "U2") (pin "28") (pinfunction "IO35_28") (pintype "passive+no_connect"))
    )
    (net (code "109") (name "unconnected-(U2-IO36-Pad29)") (class "Default")
      (node (ref "U2") (pin "29") (pinfunction "IO36_29") (pintype "passive+no_connect"))
    )
    (net (code "110") (name "unconnected-(U2-IO37-Pad30)") (class "Default")
      (node (ref "U2") (pin "30") (pinfunction "IO37_30") (pintype "passive+no_connect"))
    )
    (net (code "111") (name "unconnected-(U2-IO47-Pad24)") (class "Default")
      (node (ref "U2") (pin "24") (pinfunction "IO47_24") (pintype "passive"))
    )
    (net (code "112") (name "unconnected-(U2-IO48-Pad25)") (class "Default")
      (node (ref "U2") (pin "25") (pinfunction "IO48_25") (pintype "passive"))
    )
    (net (code "113") (name "unconnected-(U3-DO-Pad1)") (class "Default")
      (node (ref "U3") (pin "1") (pinfunction "DO_1") (pintype "output+no_connect"))
    )
    (net (code "114") (name "unconnected-(U6-ALERT{slash}RDY-Pad2)") (class "Default")
      (node (ref "U6") (pin "2") (pinfunction "ALERT/RDY_2") (pintype "passive+no_connect"))
    )
    (net (code "115") (name "unconnected-(U7-NC-Pad6)") (class "Default")
      (node (ref "U7") (pin "6") (pinfunction "NC_6") (pintype "passive"))
    )
    (net (code "116") (name "unconnected-(U8-TAB-Pad4)") (class "Default")
      (node (ref "U8") (pin "4") (pinfunction "TAB_4") (pintype "passive"))
    )
    (net (code "117") (name "unconnected-(U9-TAB-Pad4)") (class "Default")
      (node (ref "U9") (pin "4") (pinfunction "TAB_4") (pintype "passive"))
    )
    (net (code "118") (name "unconnected-(U11-ALERT{slash}RDY-Pad2)") (class "Default")
      (node (ref "U11") (pin "2") (pinfunction "ALERT/RDY_2") (pintype "passive+no_connect"))
    )
    (net (code "119") (name "unconnected-(U12-ALERT-Pad3)") (class "Default")
      (node (ref "U12") (pin "3") (pinfunction "ALERT_3") (pintype "passive+no_connect"))
    )
    (net (code "120") (name "unconnected-(U13-RDY{slash}~{BSY}-Pad5)") (class "Default")
      (node (ref "U13") (pin "5") (pinfunction "RDY/~{BSY}_5") (pintype "passive+no_connect"))
    )
    (net (code "121") (name "unconnected-(U15-ALERT-Pad3)") (class "Default")
      (node (ref "U15") (pin "3") (pinfunction "ALERT_3") (pintype "passive+no_connect"))
    )
    (net (code "122") (name "unconnected-(USB1-SBU1-PadA8)") (class "Default")
      (node (ref "USB1") (pin "A8") (pinfunction "SBU1_A8") (pintype "passive+no_connect"))
    )
    (net (code "123") (name "unconnected-(USB1-SBU2-PadB8)") (class "Default")
      (node (ref "USB1") (pin "B8") (pinfunction "SBU2_B8") (pintype "passive+no_connect"))
    )
  )
)
